# PCB_3U_SMA.net
KiCad netlist of a schematic drawn in Altium Designer
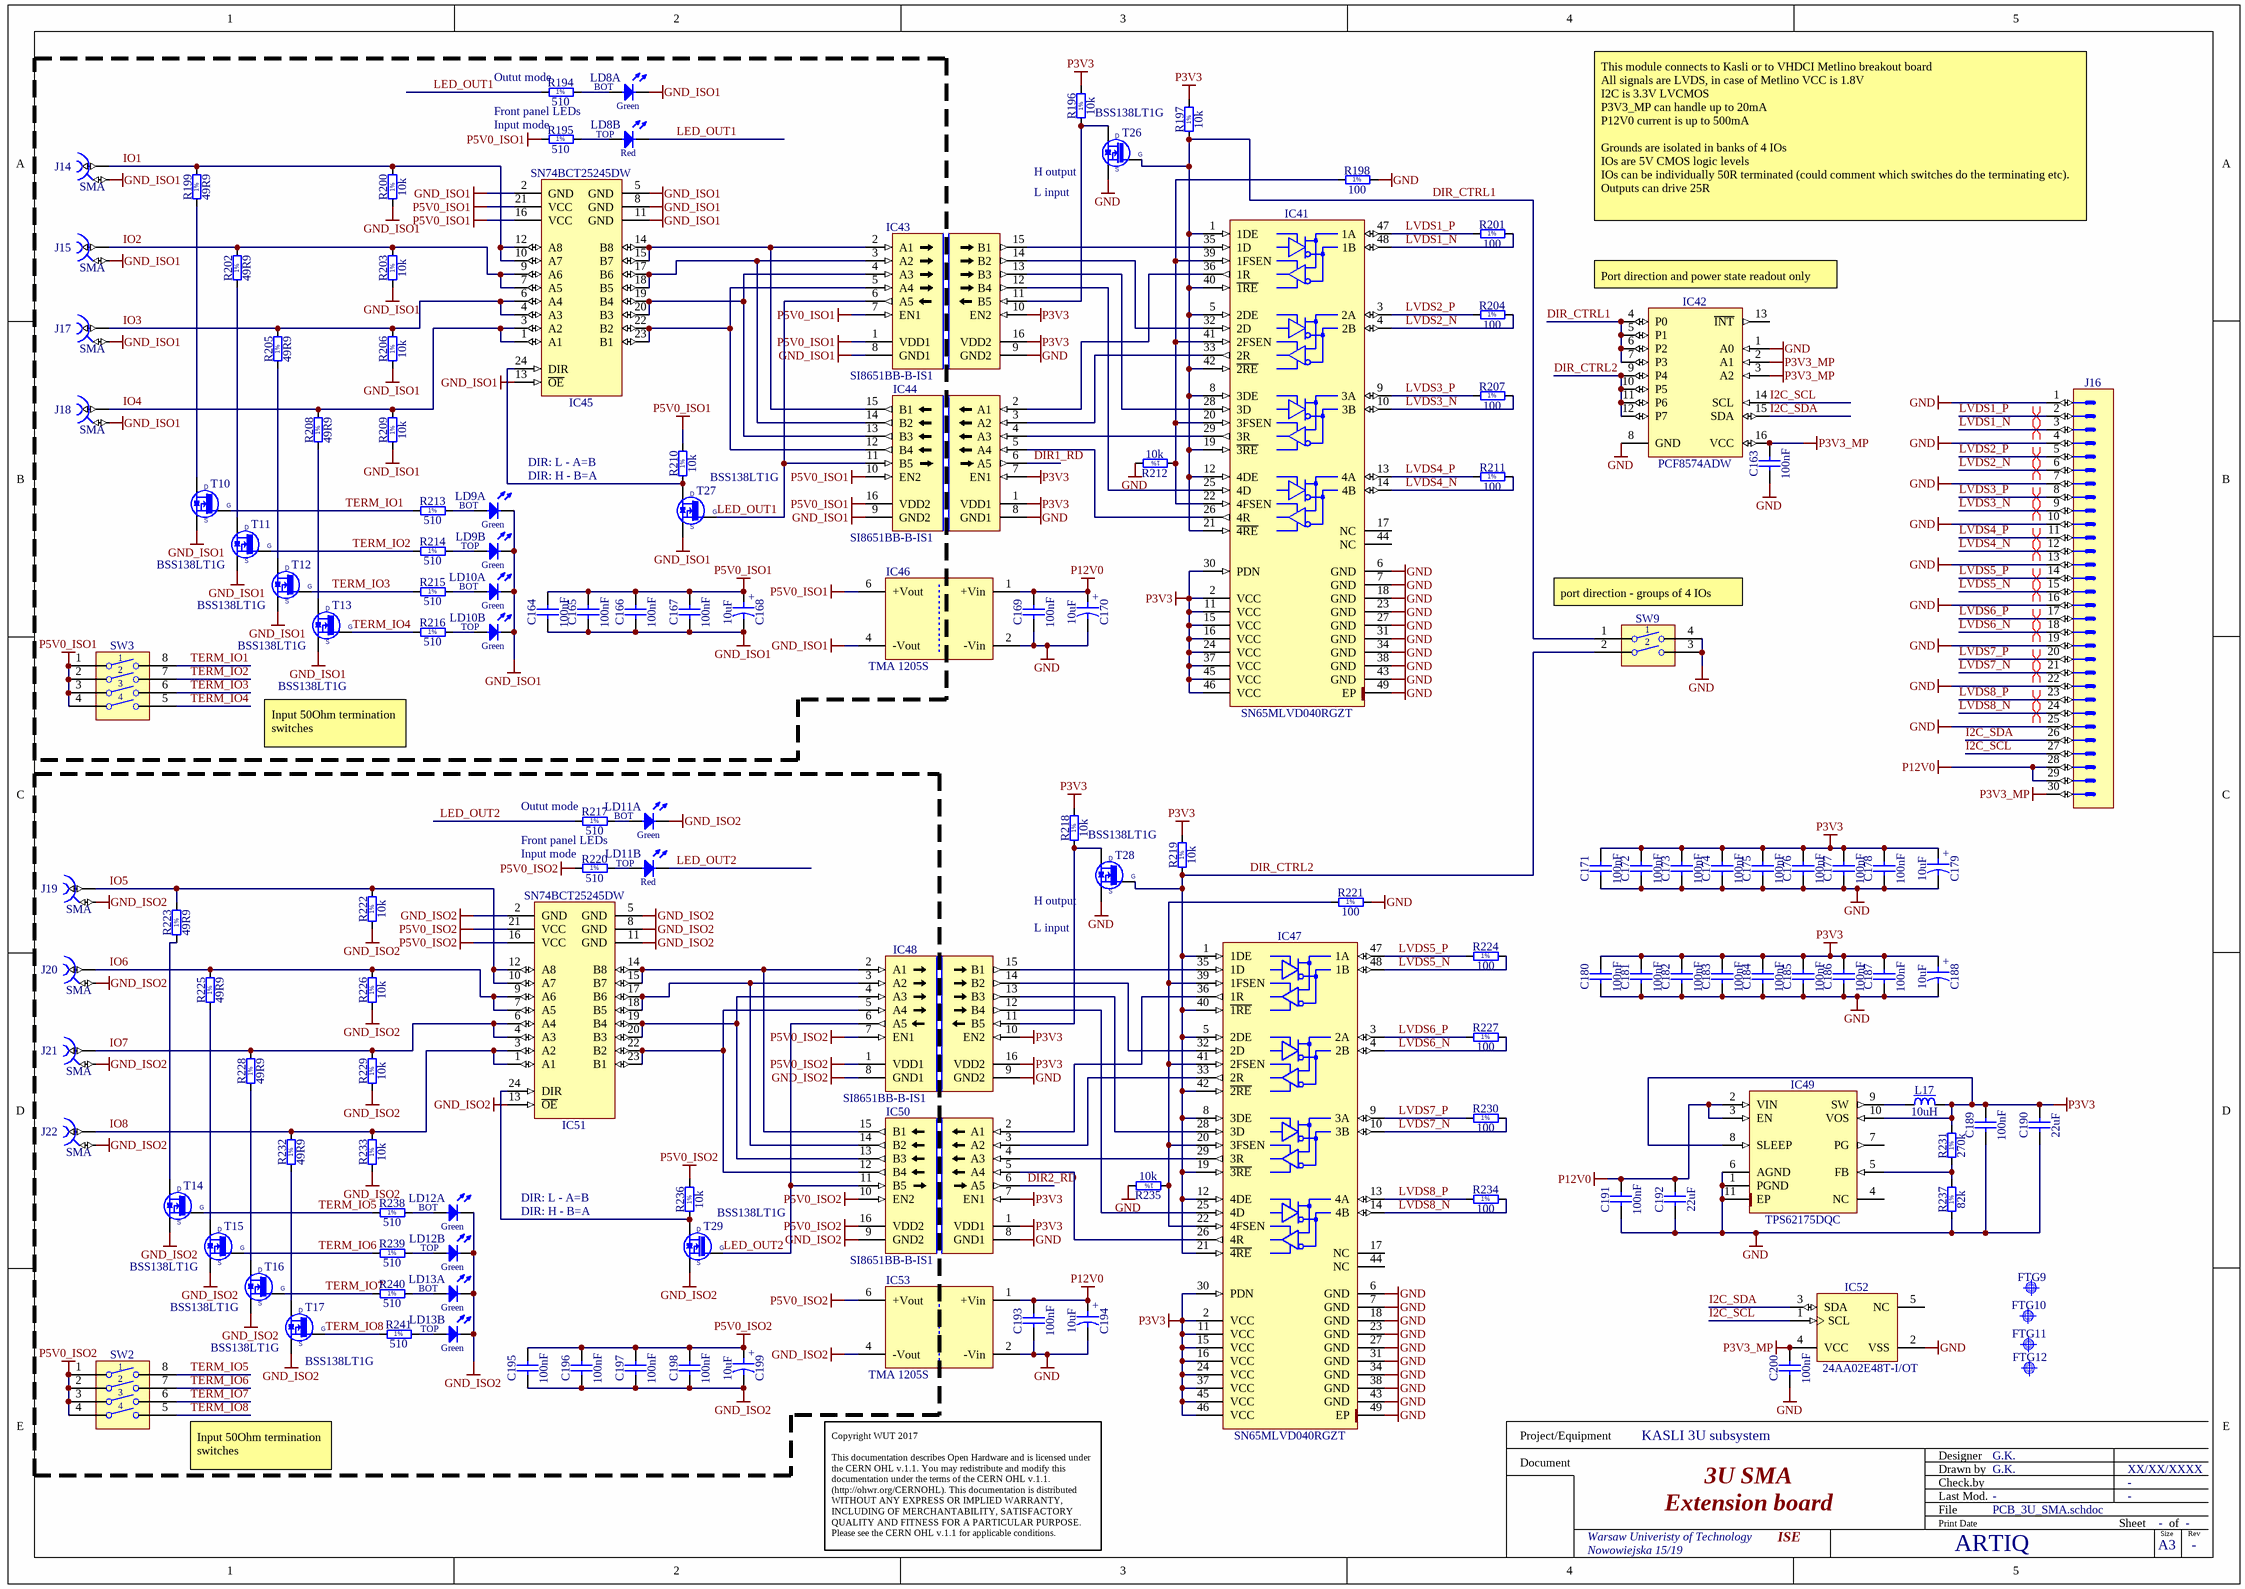
[diagram p0: PCB_3U_SMA.schdoc]

(export (version "E")
  (design (tool "Eeschema 10.0.6"))
  (components
    (comp (ref "C163")
      (value "100nF")
      (footprint "CAPC1005X55N")
      (description "Non-polarised capacitor")
      (fields
        (field (name "PART NUMBER") "CC0402_100NF_16V_10%_X5R")
        (field (name "VOLTAGE") "16V")
        (field (name "AUTHOR") "CERN DEM JLC")
      )
      (libsource (lib "Capacitors") (part "Capacitor - non polarized"))
    )
    (comp (ref "C164")
      (value "100nF")
      (footprint "CAPC1005X55N")
      (description "Non-polarised capacitor")
      (fields
        (field (name "PART NUMBER") "CC0402_100NF_16V_10%_X5R")
        (field (name "VOLTAGE") "16V")
        (field (name "AUTHOR") "CERN DEM JLC")
      )
      (libsource (lib "Capacitors") (part "Capacitor - non polarized"))
    )
    (comp (ref "C165")
      (value "100nF")
      (footprint "CAPC1005X55N")
      (description "Non-polarised capacitor")
      (fields
        (field (name "PART NUMBER") "CC0402_100NF_16V_10%_X5R")
        (field (name "VOLTAGE") "16V")
        (field (name "AUTHOR") "CERN DEM JLC")
      )
      (libsource (lib "Capacitors") (part "Capacitor - non polarized"))
    )
    (comp (ref "C166")
      (value "100nF")
      (footprint "CAPC1005X55N")
      (description "Non-polarised capacitor")
      (fields
        (field (name "PART NUMBER") "CC0402_100NF_16V_10%_X5R")
        (field (name "VOLTAGE") "16V")
        (field (name "AUTHOR") "CERN DEM JLC")
      )
      (libsource (lib "Capacitors") (part "Capacitor - non polarized"))
    )
    (comp (ref "C167")
      (value "100nF")
      (footprint "CAPC1005X55N")
      (description "Non-polarised capacitor")
      (fields
        (field (name "PART NUMBER") "CC0402_100NF_16V_10%_X5R")
        (field (name "VOLTAGE") "16V")
        (field (name "AUTHOR") "CERN DEM JLC")
      )
      (libsource (lib "Capacitors") (part "Capacitor - non polarized"))
    )
    (comp (ref "C168")
      (value "10uF")
      (footprint "CAPAE430X540N")
      (description "Polarised capacitor")
      (fields
        (field (name "PART NUMBER") "CAE430-540_10UF_16V_20%")
        (field (name "VOLTAGE") "16V")
        (field (name "AUTHOR") "CERN DEM JLC")
      )
      (libsource (lib "Capacitors") (part "Capacitor - polarized"))
    )
    (comp (ref "C169")
      (value "100nF")
      (footprint "CAPC1005X55N")
      (description "Non-polarised capacitor")
      (fields
        (field (name "PART NUMBER") "CC0402_100NF_16V_10%_X5R")
        (field (name "VOLTAGE") "16V")
        (field (name "AUTHOR") "CERN DEM JLC")
      )
      (libsource (lib "Capacitors") (part "Capacitor - non polarized"))
    )
    (comp (ref "C170")
      (value "10uF")
      (footprint "CAPAE430X540N")
      (description "Polarised capacitor")
      (fields
        (field (name "PART NUMBER") "CAE430-540_10UF_16V_20%")
        (field (name "VOLTAGE") "16V")
        (field (name "AUTHOR") "CERN DEM JLC")
      )
      (libsource (lib "Capacitors") (part "Capacitor - polarized"))
    )
    (comp (ref "C171")
      (value "100nF")
      (footprint "CAPC1005X55N")
      (description "Non-polarised capacitor")
      (fields
        (field (name "PART NUMBER") "CC0402_100NF_16V_10%_X5R")
        (field (name "VOLTAGE") "16V")
        (field (name "AUTHOR") "CERN DEM JLC")
      )
      (libsource (lib "Capacitors") (part "Capacitor - non polarized"))
    )
    (comp (ref "C172")
      (value "100nF")
      (footprint "CAPC1005X55N")
      (description "Non-polarised capacitor")
      (fields
        (field (name "PART NUMBER") "CC0402_100NF_16V_10%_X5R")
        (field (name "VOLTAGE") "16V")
        (field (name "AUTHOR") "CERN DEM JLC")
      )
      (libsource (lib "Capacitors") (part "Capacitor - non polarized"))
    )
    (comp (ref "C173")
      (value "100nF")
      (footprint "CAPC1005X55N")
      (description "Non-polarised capacitor")
      (fields
        (field (name "PART NUMBER") "CC0402_100NF_16V_10%_X5R")
        (field (name "VOLTAGE") "16V")
        (field (name "AUTHOR") "CERN DEM JLC")
      )
      (libsource (lib "Capacitors") (part "Capacitor - non polarized"))
    )
    (comp (ref "C174")
      (value "100nF")
      (footprint "CAPC1005X55N")
      (description "Non-polarised capacitor")
      (fields
        (field (name "PART NUMBER") "CC0402_100NF_16V_10%_X5R")
        (field (name "VOLTAGE") "16V")
        (field (name "AUTHOR") "CERN DEM JLC")
      )
      (libsource (lib "Capacitors") (part "Capacitor - non polarized"))
    )
    (comp (ref "C175")
      (value "100nF")
      (footprint "CAPC1005X55N")
      (description "Non-polarised capacitor")
      (fields
        (field (name "PART NUMBER") "CC0402_100NF_16V_10%_X5R")
        (field (name "VOLTAGE") "16V")
        (field (name "AUTHOR") "CERN DEM JLC")
      )
      (libsource (lib "Capacitors") (part "Capacitor - non polarized"))
    )
    (comp (ref "C176")
      (value "100nF")
      (footprint "CAPC1005X55N")
      (description "Non-polarised capacitor")
      (fields
        (field (name "PART NUMBER") "CC0402_100NF_16V_10%_X5R")
        (field (name "VOLTAGE") "16V")
        (field (name "AUTHOR") "CERN DEM JLC")
      )
      (libsource (lib "Capacitors") (part "Capacitor - non polarized"))
    )
    (comp (ref "C177")
      (value "100nF")
      (footprint "CAPC1005X55N")
      (description "Non-polarised capacitor")
      (fields
        (field (name "PART NUMBER") "CC0402_100NF_16V_10%_X5R")
        (field (name "VOLTAGE") "16V")
        (field (name "AUTHOR") "CERN DEM JLC")
      )
      (libsource (lib "Capacitors") (part "Capacitor - non polarized"))
    )
    (comp (ref "C178")
      (value "100nF")
      (footprint "CAPC1005X55N")
      (description "Non-polarised capacitor")
      (fields
        (field (name "PART NUMBER") "CC0402_100NF_16V_10%_X5R")
        (field (name "VOLTAGE") "16V")
        (field (name "AUTHOR") "CERN DEM JLC")
      )
      (libsource (lib "Capacitors") (part "Capacitor - non polarized"))
    )
    (comp (ref "C179")
      (value "10uF")
      (footprint "CAPAE430X540N")
      (description "Polarised capacitor")
      (fields
        (field (name "PART NUMBER") "CAE430-540_10UF_16V_20%")
        (field (name "VOLTAGE") "16V")
        (field (name "AUTHOR") "CERN DEM JLC")
      )
      (libsource (lib "Capacitors") (part "Capacitor - polarized"))
    )
    (comp (ref "C180")
      (value "100nF")
      (footprint "CAPC1005X55N")
      (description "Non-polarised capacitor")
      (fields
        (field (name "PART NUMBER") "CC0402_100NF_16V_10%_X5R")
        (field (name "VOLTAGE") "16V")
        (field (name "AUTHOR") "CERN DEM JLC")
      )
      (libsource (lib "Capacitors") (part "Capacitor - non polarized"))
    )
    (comp (ref "C181")
      (value "100nF")
      (footprint "CAPC1005X55N")
      (description "Non-polarised capacitor")
      (fields
        (field (name "PART NUMBER") "CC0402_100NF_16V_10%_X5R")
        (field (name "VOLTAGE") "16V")
        (field (name "AUTHOR") "CERN DEM JLC")
      )
      (libsource (lib "Capacitors") (part "Capacitor - non polarized"))
    )
    (comp (ref "C182")
      (value "100nF")
      (footprint "CAPC1005X55N")
      (description "Non-polarised capacitor")
      (fields
        (field (name "PART NUMBER") "CC0402_100NF_16V_10%_X5R")
        (field (name "VOLTAGE") "16V")
        (field (name "AUTHOR") "CERN DEM JLC")
      )
      (libsource (lib "Capacitors") (part "Capacitor - non polarized"))
    )
    (comp (ref "C183")
      (value "100nF")
      (footprint "CAPC1005X55N")
      (description "Non-polarised capacitor")
      (fields
        (field (name "PART NUMBER") "CC0402_100NF_16V_10%_X5R")
        (field (name "VOLTAGE") "16V")
        (field (name "AUTHOR") "CERN DEM JLC")
      )
      (libsource (lib "Capacitors") (part "Capacitor - non polarized"))
    )
    (comp (ref "C184")
      (value "100nF")
      (footprint "CAPC1005X55N")
      (description "Non-polarised capacitor")
      (fields
        (field (name "PART NUMBER") "CC0402_100NF_16V_10%_X5R")
        (field (name "VOLTAGE") "16V")
        (field (name "AUTHOR") "CERN DEM JLC")
      )
      (libsource (lib "Capacitors") (part "Capacitor - non polarized"))
    )
    (comp (ref "C185")
      (value "100nF")
      (footprint "CAPC1005X55N")
      (description "Non-polarised capacitor")
      (fields
        (field (name "PART NUMBER") "CC0402_100NF_16V_10%_X5R")
        (field (name "VOLTAGE") "16V")
        (field (name "AUTHOR") "CERN DEM JLC")
      )
      (libsource (lib "Capacitors") (part "Capacitor - non polarized"))
    )
    (comp (ref "C186")
      (value "100nF")
      (footprint "CAPC1005X55N")
      (description "Non-polarised capacitor")
      (fields
        (field (name "PART NUMBER") "CC0402_100NF_16V_10%_X5R")
        (field (name "VOLTAGE") "16V")
        (field (name "AUTHOR") "CERN DEM JLC")
      )
      (libsource (lib "Capacitors") (part "Capacitor - non polarized"))
    )
    (comp (ref "C187")
      (value "100nF")
      (footprint "CAPC1005X55N")
      (description "Non-polarised capacitor")
      (fields
        (field (name "PART NUMBER") "CC0402_100NF_16V_10%_X5R")
        (field (name "VOLTAGE") "16V")
        (field (name "AUTHOR") "CERN DEM JLC")
      )
      (libsource (lib "Capacitors") (part "Capacitor - non polarized"))
    )
    (comp (ref "C188")
      (value "10uF")
      (footprint "CAPAE430X540N")
      (description "Polarised capacitor")
      (fields
        (field (name "PART NUMBER") "CAE430-540_10UF_16V_20%")
        (field (name "VOLTAGE") "16V")
        (field (name "AUTHOR") "CERN DEM JLC")
      )
      (libsource (lib "Capacitors") (part "Capacitor - polarized"))
    )
    (comp (ref "C189")
      (value "100nF")
      (footprint "CAPC1005X55N")
      (description "Non-polarised capacitor")
      (fields
        (field (name "PART NUMBER") "CC0402_100NF_16V_10%_X5R")
        (field (name "VOLTAGE") "16V")
        (field (name "AUTHOR") "CERN DEM JLC")
      )
      (libsource (lib "Capacitors") (part "Capacitor - non polarized"))
    )
    (comp (ref "C190")
      (value "22uF")
      (footprint "CAPC2012X135N")
      (description "Non-polarised capacitor")
      (fields
        (field (name "PART NUMBER") "CC0805_22UF_16V_10%_X5R")
        (field (name "VOLTAGE") "16V")
        (field (name "AUTHOR") "CERN DEM JLC")
      )
      (libsource (lib "Capacitors") (part "Capacitor - non polarized"))
    )
    (comp (ref "C191")
      (value "100nF")
      (footprint "CAPC1005X55N")
      (description "Non-polarised capacitor")
      (fields
        (field (name "PART NUMBER") "CC0402_100NF_16V_10%_X5R")
        (field (name "VOLTAGE") "16V")
        (field (name "AUTHOR") "CERN DEM JLC")
      )
      (libsource (lib "Capacitors") (part "Capacitor - non polarized"))
    )
    (comp (ref "C192")
      (value "22uF")
      (footprint "CAPC2012X135N")
      (description "Non-polarised capacitor")
      (fields
        (field (name "PART NUMBER") "CC0805_22UF_16V_10%_X5R")
        (field (name "VOLTAGE") "16V")
        (field (name "AUTHOR") "CERN DEM JLC")
      )
      (libsource (lib "Capacitors") (part "Capacitor - non polarized"))
    )
    (comp (ref "C193")
      (value "100nF")
      (footprint "CAPC1005X55N")
      (description "Non-polarised capacitor")
      (fields
        (field (name "PART NUMBER") "CC0402_100NF_16V_10%_X5R")
        (field (name "VOLTAGE") "16V")
        (field (name "AUTHOR") "CERN DEM JLC")
      )
      (libsource (lib "Capacitors") (part "Capacitor - non polarized"))
    )
    (comp (ref "C194")
      (value "10uF")
      (footprint "CAPAE430X540N")
      (description "Polarised capacitor")
      (fields
        (field (name "PART NUMBER") "CAE430-540_10UF_16V_20%")
        (field (name "VOLTAGE") "16V")
        (field (name "AUTHOR") "CERN DEM JLC")
      )
      (libsource (lib "Capacitors") (part "Capacitor - polarized"))
    )
    (comp (ref "C195")
      (value "100nF")
      (footprint "CAPC1005X55N")
      (description "Non-polarised capacitor")
      (fields
        (field (name "PART NUMBER") "CC0402_100NF_16V_10%_X5R")
        (field (name "VOLTAGE") "16V")
        (field (name "AUTHOR") "CERN DEM JLC")
      )
      (libsource (lib "Capacitors") (part "Capacitor - non polarized"))
    )
    (comp (ref "C196")
      (value "100nF")
      (footprint "CAPC1005X55N")
      (description "Non-polarised capacitor")
      (fields
        (field (name "PART NUMBER") "CC0402_100NF_16V_10%_X5R")
        (field (name "VOLTAGE") "16V")
        (field (name "AUTHOR") "CERN DEM JLC")
      )
      (libsource (lib "Capacitors") (part "Capacitor - non polarized"))
    )
    (comp (ref "C197")
      (value "100nF")
      (footprint "CAPC1005X55N")
      (description "Non-polarised capacitor")
      (fields
        (field (name "PART NUMBER") "CC0402_100NF_16V_10%_X5R")
        (field (name "VOLTAGE") "16V")
        (field (name "AUTHOR") "CERN DEM JLC")
      )
      (libsource (lib "Capacitors") (part "Capacitor - non polarized"))
    )
    (comp (ref "C198")
      (value "100nF")
      (footprint "CAPC1005X55N")
      (description "Non-polarised capacitor")
      (fields
        (field (name "PART NUMBER") "CC0402_100NF_16V_10%_X5R")
        (field (name "VOLTAGE") "16V")
        (field (name "AUTHOR") "CERN DEM JLC")
      )
      (libsource (lib "Capacitors") (part "Capacitor - non polarized"))
    )
    (comp (ref "C199")
      (value "10uF")
      (footprint "CAPAE430X540N")
      (description "Polarised capacitor")
      (fields
        (field (name "PART NUMBER") "CAE430-540_10UF_16V_20%")
        (field (name "VOLTAGE") "16V")
        (field (name "AUTHOR") "CERN DEM JLC")
      )
      (libsource (lib "Capacitors") (part "Capacitor - polarized"))
    )
    (comp (ref "C200")
      (value "100nF")
      (footprint "CAPC1005X55N")
      (description "Non-polarised capacitor")
      (fields
        (field (name "PART NUMBER") "CC0402_100NF_16V_10%_X5R")
        (field (name "VOLTAGE") "16V")
        (field (name "AUTHOR") "CERN DEM JLC")
      )
      (libsource (lib "Capacitors") (part "Capacitor - non polarized"))
    )
    (comp (ref "FTG9")
      (value "Use only in PCB")
      (footprint "FIDUCIAL_TOP_C100-200")
      (description "Fiducial Target")
      (fields (field (name "PART NUMBER") "FIDUCIAL_TARGET_C100-200") (field (name "AUTHOR") "CERN DEM JLC"))
      (libsource (lib "Eletro-mechanical") (part "Fiducial Target"))
    )
    (comp (ref "FTG10")
      (value "Use only in PCB")
      (footprint "FIDUCIAL_TOP_S100-200")
      (description "Fiducial Target")
      (fields (field (name "PART NUMBER") "FIDUCIAL_TARGET_S100-200") (field (name "AUTHOR") "CERN DEM JLC"))
      (libsource (lib "Eletro-mechanical") (part "Fiducial Target"))
    )
    (comp (ref "FTG11")
      (value "Use only in PCB")
      (footprint "FIDUCIAL_TOP_S200-400")
      (description "Fiducial Target")
      (fields (field (name "PART NUMBER") "FIDUCIAL_TARGET_S200-400") (field (name "AUTHOR") "CERN DEM JLC"))
      (libsource (lib "Eletro-mechanical") (part "Fiducial Target"))
    )
    (comp (ref "FTG12")
      (value "Use only in PCB")
      (footprint "FIDUCIAL_TOP_S100-200")
      (description "Fiducial Target")
      (fields (field (name "PART NUMBER") "FIDUCIAL_TARGET_S100-200") (field (name "AUTHOR") "CERN DEM JLC"))
      (libsource (lib "Eletro-mechanical") (part "Fiducial Target"))
    )
    (comp (ref "IC41")
      (value "SN65MLVD040RGZT")
      (footprint "QFN50P700X700X100-49N-S420")
      (description "4-Channel Half-Duplex M-LVDS Line Transceiver")
      (fields (field (name "MANUFACTURER") "TEXAS INSTRUMENTS") (field (name "AUTHOR") "CERN DEM JLC"))
      (libsource (lib "ICs And Semiconductors") (part "SN65MLVD040"))
    )
    (comp (ref "IC42")
      (value "PCF8574ADW")
      (footprint "SOIC127P1030X265-16N")
      (description "Remote 8-bit I/O Expander For I2C Bus")
      (fields (field (name "MANUFACTURER") "TEXAS INSTRUMENTS") (field (name "AUTHOR") "CERN DEM JLC"))
      (libsource (lib "ICs And Semiconductors") (part "PCF8574ADW"))
    )
    (comp (ref "IC43")
      (value "SI8651BB-B-IS1")
      (footprint "SOIC127P600X175-16N")
      (description "Low Power Five-Channel Digital Isolator")
      (fields (field (name "MANUFACTURER") "SILICON LABS") (field (name "AUTHOR") "CERN DEM JLC"))
      (libsource (lib "") (part "Si8651_1"))
    )
    (comp (ref "IC44")
      (value "SI8651BB-B-IS1")
      (footprint "SOIC127P600X175-16N")
      (description "Low Power Five-Channel Digital Isolator")
      (fields (field (name "MANUFACTURER") "SILICON LABS") (field (name "AUTHOR") "CERN DEM JLC"))
      (libsource (lib "ICs And Semiconductors") (part "Si8651"))
    )
    (comp (ref "IC45")
      (value "SN74BCT25245DW")
      (footprint "SOIC127P1030X265-24N")
      (description "25 Ohms Octal Bus Transceiver With 3-State Outputs")
      (fields (field (name "MANUFACTURER") "TEXAS INSTRUMENTS") (field (name "AUTHOR") "CERN DEM JLC"))
      (libsource (lib "ICs And Semiconductors") (part "7425245"))
    )
    (comp (ref "IC46")
      (value "TMA 1205S")
      (footprint "DCDC_TRACO_TMA")
      (description "1 W Watt, 10.8-13.2VDCVin, 5 V@0.2 A")
      (fields (field (name "MANUFACTURER") "TRACO POWER") (field (name "AUTHOR") "GK"))
      (libsource (lib "LIBRARY_SCH") (part "DC/DC_TRACO_TMA1205S"))
    )
    (comp (ref "IC47")
      (value "SN65MLVD040RGZT")
      (footprint "QFN50P700X700X100-49N-S420")
      (description "4-Channel Half-Duplex M-LVDS Line Transceiver")
      (fields (field (name "MANUFACTURER") "TEXAS INSTRUMENTS") (field (name "AUTHOR") "CERN DEM JLC"))
      (libsource (lib "ICs And Semiconductors") (part "SN65MLVD040"))
    )
    (comp (ref "IC48")
      (value "SI8651BB-B-IS1")
      (footprint "SOIC127P600X175-16N")
      (description "Low Power Five-Channel Digital Isolator")
      (fields (field (name "MANUFACTURER") "SILICON LABS") (field (name "AUTHOR") "CERN DEM JLC"))
      (libsource (lib "") (part "Si8651_1"))
    )
    (comp (ref "IC49")
      (value "TPS62175DQC")
      (footprint "SON50P200X300X80-11N-R94X250")
      (description "4.75-28VDC to 1-6VDC, 500mA Step-Down Converter With Sleep Mode")
      (fields (field (name "MANUFACTURER") "TEXAS INSTRUMENTS") (field (name "AUTHOR") "CERN DEM JMW"))
      (libsource (lib "ICs And Semiconductors") (part "TPS62175"))
    )
    (comp (ref "IC50")
      (value "SI8651BB-B-IS1")
      (footprint "SOIC127P600X175-16N")
      (description "Low Power Five-Channel Digital Isolator")
      (fields (field (name "MANUFACTURER") "SILICON LABS") (field (name "AUTHOR") "CERN DEM JLC"))
      (libsource (lib "ICs And Semiconductors") (part "Si8651"))
    )
    (comp (ref "IC51")
      (value "SN74BCT25245DW")
      (footprint "SOIC127P1030X265-24N")
      (description "25 Ohms Octal Bus Transceiver With 3-State Outputs")
      (fields (field (name "MANUFACTURER") "TEXAS INSTRUMENTS") (field (name "AUTHOR") "CERN DEM JLC"))
      (libsource (lib "ICs And Semiconductors") (part "7425245"))
    )
    (comp (ref "IC52")
      (value "24AA02E48T-I/OT")
      (footprint "SOT95P280X145-5N")
      (description "1.7V-5.5V, 2K I2C Serial EEPROM With EUI-48 Node Identity")
      (fields (field (name "MANUFACTURER") "MICROCHIP TECHNOLOGY") (field (name "AUTHOR") "CERN DEM MR"))
      (libsource (lib "ICs And Semiconductors") (part "24AA02E48T-I/OT"))
    )
    (comp (ref "IC53")
      (value "TMA 1205S")
      (footprint "DCDC_TRACO_TMA")
      (description "1 W Watt, 10.8-13.2VDCVin, 5 V@0.2 A")
      (fields (field (name "MANUFACTURER") "TRACO POWER") (field (name "AUTHOR") "GK"))
      (libsource (lib "LIBRARY_SCH") (part "DC/DC_TRACO_TMA1205S"))
    )
    (comp (ref "J14")
      (value "SMA")
      (footprint "MOLEX_73251-2120")
      (description "50 Ohm, SMA Edge Mount PCB, With Jam Nut And Lock Washer")
      (fields
        (field (name "PART NUMBER") "MOLEX_73251-2120")
        (field (name "MANUFACTURER") "MOLEX")
        (field (name "AUTHOR") "CERN DEM JLC")
      )
      (libsource (lib "LIBRARY_SCH") (part "CON_SMA_RA_SMD_73251-2120"))
    )
    (comp (ref "J15")
      (value "SMA")
      (footprint "SMA209F")
      (description "50 Ohm Through Hole SMA Right Angle PCB Jack")
      (fields
        (field (name "PART NUMBER") "SMA209F")
        (field (name "MANUFACTURER") "S-Conn")
        (field (name "AUTHOR") "GK")
      )
      (libsource (lib "LIBRARY_SCH") (part "CON_SMA_SMA209F"))
    )
    (comp (ref "J16")
      (value "~")
      (footprint "3M_N2530-6002RB")
      (description "Connector 30 Male")
      (fields
        (field (name "PART NUMBER") "3M_N2530-6002RB")
        (field (name "MANUFACTURER") "3M")
        (field (name "AUTHOR") "CERN DEM JLC")
      )
      (libsource (lib "Connectors") (part "Connector 30 Male"))
    )
    (comp (ref "J17")
      (value "SMA")
      (footprint "MOLEX_73251-2120")
      (description "50 Ohm, SMA Edge Mount PCB, With Jam Nut And Lock Washer")
      (fields
        (field (name "PART NUMBER") "MOLEX_73251-2120")
        (field (name "MANUFACTURER") "MOLEX")
        (field (name "AUTHOR") "CERN DEM JLC")
      )
      (libsource (lib "LIBRARY_SCH") (part "CON_SMA_RA_SMD_73251-2120"))
    )
    (comp (ref "J18")
      (value "SMA")
      (footprint "SMA209F")
      (description "50 Ohm Through Hole SMA Right Angle PCB Jack")
      (fields
        (field (name "PART NUMBER") "SMA209F")
        (field (name "MANUFACTURER") "S-Conn")
        (field (name "AUTHOR") "GK")
      )
      (libsource (lib "LIBRARY_SCH") (part "CON_SMA_SMA209F"))
    )
    (comp (ref "J19")
      (value "SMA")
      (footprint "MOLEX_73251-2120")
      (description "50 Ohm, SMA Edge Mount PCB, With Jam Nut And Lock Washer")
      (fields
        (field (name "PART NUMBER") "MOLEX_73251-2120")
        (field (name "MANUFACTURER") "MOLEX")
        (field (name "AUTHOR") "CERN DEM JLC")
      )
      (libsource (lib "LIBRARY_SCH") (part "CON_SMA_RA_SMD_73251-2120"))
    )
    (comp (ref "J20")
      (value "SMA")
      (footprint "SMA209F")
      (description "50 Ohm Through Hole SMA Right Angle PCB Jack")
      (fields
        (field (name "PART NUMBER") "SMA209F")
        (field (name "MANUFACTURER") "S-Conn")
        (field (name "AUTHOR") "GK")
      )
      (libsource (lib "LIBRARY_SCH") (part "CON_SMA_SMA209F"))
    )
    (comp (ref "J21")
      (value "SMA")
      (footprint "MOLEX_73251-2120")
      (description "50 Ohm, SMA Edge Mount PCB, With Jam Nut And Lock Washer")
      (fields
        (field (name "PART NUMBER") "MOLEX_73251-2120")
        (field (name "MANUFACTURER") "MOLEX")
        (field (name "AUTHOR") "CERN DEM JLC")
      )
      (libsource (lib "LIBRARY_SCH") (part "CON_SMA_RA_SMD_73251-2120"))
    )
    (comp (ref "J22")
      (value "SMA")
      (footprint "SMA209F")
      (description "50 Ohm Through Hole SMA Right Angle PCB Jack")
      (fields
        (field (name "PART NUMBER") "SMA209F")
        (field (name "MANUFACTURER") "S-Conn")
        (field (name "AUTHOR") "GK")
      )
      (libsource (lib "LIBRARY_SCH") (part "CON_SMA_SMA209F"))
    )
    (comp (ref "L17")
      (value "10uH")
      (footprint "IND_MURATA-PS_8400")
      (description "Inductor With Core")
      (fields
        (field (name "PART NUMBER") "IND_10UH_10%_MURATA-PS_8400")
        (field (name "POWER") "950mA")
        (field (name "AUTHOR") "CERN DEM JLC")
      )
      (libsource (lib "Inductors & Transformers") (part "Inductor With Magnetic core"))
    )
    (comp (ref "LD8")
      (value "Red/Green")
      (footprint "LED_DIALIGHT_571-0112F")
      (description "2x LED  Botom Green, Top Red")
      (fields
        (field (name "PART NUMBER") "LED_DIALIGHT_571-0112F")
        (field (name "MANUFACTURER") "DIALIGHT")
        (field (name "AUTHOR") "CERN DEM JLC")
      )
      (libsource (lib "ICs And Semiconductors") (part "LED x2 G-1C2A-BOT_R-3C4A-TOP"))
    )
    (comp (ref "LD9")
      (value "Green/Green")
      (footprint "LED_DIALIGHT_571-0122F")
      (description "LED x2 Green 1C2A-BOT_3C4A-TOP")
      (fields
        (field (name "PART NUMBER") "LED_DIALIGHT_571-0122F")
        (field (name "MANUFACTURER") "DIALIGHT")
        (field (name "AUTHOR") "CERN DEM JLC")
      )
      (libsource (lib "ICs And Semiconductors") (part "LED x2 Green 1C2A-BOT_3C4A-TOP"))
    )
    (comp (ref "LD10")
      (value "Green/Green")
      (footprint "LED_DIALIGHT_571-0122F")
      (description "LED x2 Green 1C2A-BOT_3C4A-TOP")
      (fields
        (field (name "PART NUMBER") "LED_DIALIGHT_571-0122F")
        (field (name "MANUFACTURER") "DIALIGHT")
        (field (name "AUTHOR") "CERN DEM JLC")
      )
      (libsource (lib "ICs And Semiconductors") (part "LED x2 Green 1C2A-BOT_3C4A-TOP"))
    )
    (comp (ref "LD11")
      (value "Red/Green")
      (footprint "LED_DIALIGHT_571-0112F")
      (description "2x LED  Botom Green, Top Red")
      (fields
        (field (name "PART NUMBER") "LED_DIALIGHT_571-0112F")
        (field (name "MANUFACTURER") "DIALIGHT")
        (field (name "AUTHOR") "CERN DEM JLC")
      )
      (libsource (lib "ICs And Semiconductors") (part "LED x2 G-1C2A-BOT_R-3C4A-TOP"))
    )
    (comp (ref "LD12")
      (value "Green/Green")
      (footprint "LED_DIALIGHT_571-0122F")
      (description "LED x2 Green 1C2A-BOT_3C4A-TOP")
      (fields
        (field (name "PART NUMBER") "LED_DIALIGHT_571-0122F")
        (field (name "MANUFACTURER") "DIALIGHT")
        (field (name "AUTHOR") "CERN DEM JLC")
      )
      (libsource (lib "ICs And Semiconductors") (part "LED x2 Green 1C2A-BOT_3C4A-TOP"))
    )
    (comp (ref "LD13")
      (value "Green/Green")
      (footprint "LED_DIALIGHT_571-0122F")
      (description "LED x2 Green 1C2A-BOT_3C4A-TOP")
      (fields
        (field (name "PART NUMBER") "LED_DIALIGHT_571-0122F")
        (field (name "MANUFACTURER") "DIALIGHT")
        (field (name "AUTHOR") "CERN DEM JLC")
      )
      (libsource (lib "ICs And Semiconductors") (part "LED x2 Green 1C2A-BOT_3C4A-TOP"))
    )
    (comp (ref "R194")
      (value "510")
      (footprint "RESC1005X40N")
      (description "Resistor - 1%")
      (fields
        (field (name "PART NUMBER") "R0402_510R_1%_0.0625W_100PPM")
        (field (name "POWER") "0.0625W")
        (field (name "AUTHOR") "CERN DEM JLC")
      )
      (libsource (lib "Resistors") (part "Resistor - 1%"))
    )
    (comp (ref "R195")
      (value "510")
      (footprint "RESC1005X40N")
      (description "Resistor - 1%")
      (fields
        (field (name "PART NUMBER") "R0402_510R_1%_0.0625W_100PPM")
        (field (name "POWER") "0.0625W")
        (field (name "AUTHOR") "CERN DEM JLC")
      )
      (libsource (lib "Resistors") (part "Resistor - 1%"))
    )
    (comp (ref "R196")
      (value "10k")
      (footprint "RESC1005X40N")
      (description "Resistor - 1%")
      (fields
        (field (name "PART NUMBER") "R0402_10K_1%_0.0625W_100PPM")
        (field (name "POWER") "0.0625W")
        (field (name "AUTHOR") "CERN DEM JLC")
      )
      (libsource (lib "Resistors") (part "Resistor - 1%"))
    )
    (comp (ref "R197")
      (value "10k")
      (footprint "RESC1005X40N")
      (description "Resistor - 1%")
      (fields
        (field (name "PART NUMBER") "R0402_10K_1%_0.0625W_100PPM")
        (field (name "POWER") "0.0625W")
        (field (name "AUTHOR") "CERN DEM JLC")
      )
      (libsource (lib "Resistors") (part "Resistor - 1%"))
    )
    (comp (ref "R198")
      (value "100")
      (footprint "RESC1005X40N")
      (description "Resistor - 1%")
      (fields
        (field (name "PART NUMBER") "R0402_100R_1%_0.1W_100PPM")
        (field (name "POWER") "0.1W")
        (field (name "AUTHOR") "CERN DEM JLC")
      )
      (libsource (lib "Resistors") (part "Resistor - 1%"))
    )
    (comp (ref "R199")
      (value "49R9")
      (footprint "RESC3225X70N")
      (description "Resistor - 1%")
      (fields
        (field (name "PART NUMBER") "R1210_49R9_1%_0.5W_100PPM_VISHAY_CRCW")
        (field (name "POWER") "0.5W")
        (field (name "AUTHOR") "CERN DEM JMW")
      )
      (libsource (lib "Resistors") (part "Resistor - 1%"))
    )
    (comp (ref "R200")
      (value "10k")
      (footprint "RESC1005X40N")
      (description "Resistor - 1%")
      (fields
        (field (name "PART NUMBER") "R0402_10K_1%_0.0625W_100PPM")
        (field (name "POWER") "0.0625W")
        (field (name "AUTHOR") "CERN DEM JLC")
      )
      (libsource (lib "Resistors") (part "Resistor - 1%"))
    )
    (comp (ref "R201")
      (value "100")
      (footprint "RESC1005X40N")
      (description "Resistor - 1%")
      (fields
        (field (name "PART NUMBER") "R0402_100R_1%_0.1W_100PPM")
        (field (name "POWER") "0.1W")
        (field (name "AUTHOR") "CERN DEM JLC")
      )
      (libsource (lib "Resistors") (part "Resistor - 1%"))
    )
    (comp (ref "R202")
      (value "49R9")
      (footprint "RESC3225X70N")
      (description "Resistor - 1%")
      (fields
        (field (name "PART NUMBER") "R1210_49R9_1%_0.5W_100PPM_VISHAY_CRCW")
        (field (name "POWER") "0.5W")
        (field (name "AUTHOR") "CERN DEM JMW")
      )
      (libsource (lib "Resistors") (part "Resistor - 1%"))
    )
    (comp (ref "R203")
      (value "10k")
      (footprint "RESC1005X40N")
      (description "Resistor - 1%")
      (fields
        (field (name "PART NUMBER") "R0402_10K_1%_0.0625W_100PPM")
        (field (name "POWER") "0.0625W")
        (field (name "AUTHOR") "CERN DEM JLC")
      )
      (libsource (lib "Resistors") (part "Resistor - 1%"))
    )
    (comp (ref "R204")
      (value "100")
      (footprint "RESC1005X40N")
      (description "Resistor - 1%")
      (fields
        (field (name "PART NUMBER") "R0402_100R_1%_0.1W_100PPM")
        (field (name "POWER") "0.1W")
        (field (name "AUTHOR") "CERN DEM JLC")
      )
      (libsource (lib "Resistors") (part "Resistor - 1%"))
    )
    (comp (ref "R205")
      (value "49R9")
      (footprint "RESC3225X70N")
      (description "Resistor - 1%")
      (fields
        (field (name "PART NUMBER") "R1210_49R9_1%_0.5W_100PPM_VISHAY_CRCW")
        (field (name "POWER") "0.5W")
        (field (name "AUTHOR") "CERN DEM JMW")
      )
      (libsource (lib "Resistors") (part "Resistor - 1%"))
    )
    (comp (ref "R206")
      (value "10k")
      (footprint "RESC1005X40N")
      (description "Resistor - 1%")
      (fields
        (field (name "PART NUMBER") "R0402_10K_1%_0.0625W_100PPM")
        (field (name "POWER") "0.0625W")
        (field (name "AUTHOR") "CERN DEM JLC")
      )
      (libsource (lib "Resistors") (part "Resistor - 1%"))
    )
    (comp (ref "R207")
      (value "100")
      (footprint "RESC1005X40N")
      (description "Resistor - 1%")
      (fields
        (field (name "PART NUMBER") "R0402_100R_1%_0.1W_100PPM")
        (field (name "POWER") "0.1W")
        (field (name "AUTHOR") "CERN DEM JLC")
      )
      (libsource (lib "Resistors") (part "Resistor - 1%"))
    )
    (comp (ref "R208")
      (value "49R9")
      (footprint "RESC3225X70N")
      (description "Resistor - 1%")
      (fields
        (field (name "PART NUMBER") "R1210_49R9_1%_0.5W_100PPM_VISHAY_CRCW")
        (field (name "POWER") "0.5W")
        (field (name "AUTHOR") "CERN DEM JMW")
      )
      (libsource (lib "Resistors") (part "Resistor - 1%"))
    )
    (comp (ref "R209")
      (value "10k")
      (footprint "RESC1005X40N")
      (description "Resistor - 1%")
      (fields
        (field (name "PART NUMBER") "R0402_10K_1%_0.0625W_100PPM")
        (field (name "POWER") "0.0625W")
        (field (name "AUTHOR") "CERN DEM JLC")
      )
      (libsource (lib "Resistors") (part "Resistor - 1%"))
    )
    (comp (ref "R210")
      (value "10k")
      (footprint "RESC1005X40N")
      (description "Resistor - 1%")
      (fields
        (field (name "PART NUMBER") "R0402_10K_1%_0.0625W_100PPM")
        (field (name "POWER") "0.0625W")
        (field (name "AUTHOR") "CERN DEM JLC")
      )
      (libsource (lib "Resistors") (part "Resistor - 1%"))
    )
    (comp (ref "R211")
      (value "100")
      (footprint "RESC1005X40N")
      (description "Resistor - 1%")
      (fields
        (field (name "PART NUMBER") "R0402_100R_1%_0.1W_100PPM")
        (field (name "POWER") "0.1W")
        (field (name "AUTHOR") "CERN DEM JLC")
      )
      (libsource (lib "Resistors") (part "Resistor - 1%"))
    )
    (comp (ref "R212")
      (value "10k")
      (footprint "RESC1005X40N")
      (description "Resistor - 1%")
      (fields
        (field (name "PART NUMBER") "R0402_10K_1%_0.0625W_100PPM")
        (field (name "POWER") "0.0625W")
        (field (name "AUTHOR") "CERN DEM JLC")
      )
      (libsource (lib "Resistors") (part "Resistor - 1%"))
    )
    (comp (ref "R213")
      (value "510")
      (footprint "RESC1005X40N")
      (description "Resistor - 1%")
      (fields
        (field (name "PART NUMBER") "R0402_510R_1%_0.0625W_100PPM")
        (field (name "POWER") "0.0625W")
        (field (name "AUTHOR") "CERN DEM JLC")
      )
      (libsource (lib "Resistors") (part "Resistor - 1%"))
    )
    (comp (ref "R214")
      (value "510")
      (footprint "RESC1005X40N")
      (description "Resistor - 1%")
      (fields
        (field (name "PART NUMBER") "R0402_510R_1%_0.0625W_100PPM")
        (field (name "POWER") "0.0625W")
        (field (name "AUTHOR") "CERN DEM JLC")
      )
      (libsource (lib "Resistors") (part "Resistor - 1%"))
    )
    (comp (ref "R215")
      (value "510")
      (footprint "RESC1005X40N")
      (description "Resistor - 1%")
      (fields
        (field (name "PART NUMBER") "R0402_510R_1%_0.0625W_100PPM")
        (field (name "POWER") "0.0625W")
        (field (name "AUTHOR") "CERN DEM JLC")
      )
      (libsource (lib "Resistors") (part "Resistor - 1%"))
    )
    (comp (ref "R216")
      (value "510")
      (footprint "RESC1005X40N")
      (description "Resistor - 1%")
      (fields
        (field (name "PART NUMBER") "R0402_510R_1%_0.0625W_100PPM")
        (field (name "POWER") "0.0625W")
        (field (name "AUTHOR") "CERN DEM JLC")
      )
      (libsource (lib "Resistors") (part "Resistor - 1%"))
    )
    (comp (ref "R217")
      (value "510")
      (footprint "RESC1005X40N")
      (description "Resistor - 1%")
      (fields
        (field (name "PART NUMBER") "R0402_510R_1%_0.0625W_100PPM")
        (field (name "POWER") "0.0625W")
        (field (name "AUTHOR") "CERN DEM JLC")
      )
      (libsource (lib "Resistors") (part "Resistor - 1%"))
    )
    (comp (ref "R218")
      (value "10k")
      (footprint "RESC1005X40N")
      (description "Resistor - 1%")
      (fields
        (field (name "PART NUMBER") "R0402_10K_1%_0.0625W_100PPM")
        (field (name "POWER") "0.0625W")
        (field (name "AUTHOR") "CERN DEM JLC")
      )
      (libsource (lib "Resistors") (part "Resistor - 1%"))
    )
    (comp (ref "R219")
      (value "10k")
      (footprint "RESC1005X40N")
      (description "Resistor - 1%")
      (fields
        (field (name "PART NUMBER") "R0402_10K_1%_0.0625W_100PPM")
        (field (name "POWER") "0.0625W")
        (field (name "AUTHOR") "CERN DEM JLC")
      )
      (libsource (lib "Resistors") (part "Resistor - 1%"))
    )
    (comp (ref "R220")
      (value "510")
      (footprint "RESC1005X40N")
      (description "Resistor - 1%")
      (fields
        (field (name "PART NUMBER") "R0402_510R_1%_0.0625W_100PPM")
        (field (name "POWER") "0.0625W")
        (field (name "AUTHOR") "CERN DEM JLC")
      )
      (libsource (lib "Resistors") (part "Resistor - 1%"))
    )
    (comp (ref "R221")
      (value "100")
      (footprint "RESC1005X40N")
      (description "Resistor - 1%")
      (fields
        (field (name "PART NUMBER") "R0402_100R_1%_0.1W_100PPM")
        (field (name "POWER") "0.1W")
        (field (name "AUTHOR") "CERN DEM JLC")
      )
      (libsource (lib "Resistors") (part "Resistor - 1%"))
    )
    (comp (ref "R222")
      (value "10k")
      (footprint "RESC1005X40N")
      (description "Resistor - 1%")
      (fields
        (field (name "PART NUMBER") "R0402_10K_1%_0.0625W_100PPM")
        (field (name "POWER") "0.0625W")
        (field (name "AUTHOR") "CERN DEM JLC")
      )
      (libsource (lib "Resistors") (part "Resistor - 1%"))
    )
    (comp (ref "R223")
      (value "49R9")
      (footprint "RESC3225X70N")
      (description "Resistor - 1%")
      (fields
        (field (name "PART NUMBER") "R1210_49R9_1%_0.5W_100PPM_VISHAY_CRCW")
        (field (name "POWER") "0.5W")
        (field (name "AUTHOR") "CERN DEM JMW")
      )
      (libsource (lib "Resistors") (part "Resistor - 1%"))
    )
    (comp (ref "R224")
      (value "100")
      (footprint "RESC1005X40N")
      (description "Resistor - 1%")
      (fields
        (field (name "PART NUMBER") "R0402_100R_1%_0.1W_100PPM")
        (field (name "POWER") "0.1W")
        (field (name "AUTHOR") "CERN DEM JLC")
      )
      (libsource (lib "Resistors") (part "Resistor - 1%"))
    )
    (comp (ref "R225")
      (value "49R9")
      (footprint "RESC3225X70N")
      (description "Resistor - 1%")
      (fields
        (field (name "PART NUMBER") "R1210_49R9_1%_0.5W_100PPM_VISHAY_CRCW")
        (field (name "POWER") "0.5W")
        (field (name "AUTHOR") "CERN DEM JMW")
      )
      (libsource (lib "Resistors") (part "Resistor - 1%"))
    )
    (comp (ref "R226")
      (value "10k")
      (footprint "RESC1005X40N")
      (description "Resistor - 1%")
      (fields
        (field (name "PART NUMBER") "R0402_10K_1%_0.0625W_100PPM")
        (field (name "POWER") "0.0625W")
        (field (name "AUTHOR") "CERN DEM JLC")
      )
      (libsource (lib "Resistors") (part "Resistor - 1%"))
    )
    (comp (ref "R227")
      (value "100")
      (footprint "RESC1005X40N")
      (description "Resistor - 1%")
      (fields
        (field (name "PART NUMBER") "R0402_100R_1%_0.1W_100PPM")
        (field (name "POWER") "0.1W")
        (field (name "AUTHOR") "CERN DEM JLC")
      )
      (libsource (lib "Resistors") (part "Resistor - 1%"))
    )
    (comp (ref "R228")
      (value "49R9")
      (footprint "RESC3225X70N")
      (description "Resistor - 1%")
      (fields
        (field (name "PART NUMBER") "R1210_49R9_1%_0.5W_100PPM_VISHAY_CRCW")
        (field (name "POWER") "0.5W")
        (field (name "AUTHOR") "CERN DEM JMW")
      )
      (libsource (lib "Resistors") (part "Resistor - 1%"))
    )
    (comp (ref "R229")
      (value "10k")
      (footprint "RESC1005X40N")
      (description "Resistor - 1%")
      (fields
        (field (name "PART NUMBER") "R0402_10K_1%_0.0625W_100PPM")
        (field (name "POWER") "0.0625W")
        (field (name "AUTHOR") "CERN DEM JLC")
      )
      (libsource (lib "Resistors") (part "Resistor - 1%"))
    )
    (comp (ref "R230")
      (value "100")
      (footprint "RESC1005X40N")
      (description "Resistor - 1%")
      (fields
        (field (name "PART NUMBER") "R0402_100R_1%_0.1W_100PPM")
        (field (name "POWER") "0.1W")
        (field (name "AUTHOR") "CERN DEM JLC")
      )
      (libsource (lib "Resistors") (part "Resistor - 1%"))
    )
    (comp (ref "R231")
      (value "270k")
      (footprint "RESC1608X55N")
      (description "Resistor - 1%")
      (fields
        (field (name "PART NUMBER") "R0603_270K_1%_0.1W_100PPM")
        (field (name "POWER") "0.1W")
        (field (name "AUTHOR") "CERN DEM JLC")
      )
      (libsource (lib "Resistors") (part "Resistor - 1%"))
    )
    (comp (ref "R232")
      (value "49R9")
      (footprint "RESC3225X70N")
      (description "Resistor - 1%")
      (fields
        (field (name "PART NUMBER") "R1210_49R9_1%_0.5W_100PPM_VISHAY_CRCW")
        (field (name "POWER") "0.5W")
        (field (name "AUTHOR") "CERN DEM JMW")
      )
      (libsource (lib "Resistors") (part "Resistor - 1%"))
    )
    (comp (ref "R233")
      (value "10k")
      (footprint "RESC1005X40N")
      (description "Resistor - 1%")
      (fields
        (field (name "PART NUMBER") "R0402_10K_1%_0.0625W_100PPM")
        (field (name "POWER") "0.0625W")
        (field (name "AUTHOR") "CERN DEM JLC")
      )
      (libsource (lib "Resistors") (part "Resistor - 1%"))
    )
    (comp (ref "R234")
      (value "100")
      (footprint "RESC1005X40N")
      (description "Resistor - 1%")
      (fields
        (field (name "PART NUMBER") "R0402_100R_1%_0.1W_100PPM")
        (field (name "POWER") "0.1W")
        (field (name "AUTHOR") "CERN DEM JLC")
      )
      (libsource (lib "Resistors") (part "Resistor - 1%"))
    )
    (comp (ref "R235")
      (value "10k")
      (footprint "RESC1005X40N")
      (description "Resistor - 1%")
      (fields
        (field (name "PART NUMBER") "R0402_10K_1%_0.0625W_100PPM")
        (field (name "POWER") "0.0625W")
        (field (name "AUTHOR") "CERN DEM JLC")
      )
      (libsource (lib "Resistors") (part "Resistor - 1%"))
    )
    (comp (ref "R236")
      (value "10k")
      (footprint "RESC1005X40N")
      (description "Resistor - 1%")
      (fields
        (field (name "PART NUMBER") "R0402_10K_1%_0.0625W_100PPM")
        (field (name "POWER") "0.0625W")
        (field (name "AUTHOR") "CERN DEM JLC")
      )
      (libsource (lib "Resistors") (part "Resistor - 1%"))
    )
    (comp (ref "R237")
      (value "82k")
      (footprint "RESC1608X55N")
      (description "Resistor - 1%")
      (fields
        (field (name "PART NUMBER") "R0603_82K_1%_0.1W_100PPM")
        (field (name "POWER") "0.1W")
        (field (name "AUTHOR") "CERN DEM JLC")
      )
      (libsource (lib "Resistors") (part "Resistor - 1%"))
    )
    (comp (ref "R238")
      (value "510")
      (footprint "RESC1005X40N")
      (description "Resistor - 1%")
      (fields
        (field (name "PART NUMBER") "R0402_510R_1%_0.0625W_100PPM")
        (field (name "POWER") "0.0625W")
        (field (name "AUTHOR") "CERN DEM JLC")
      )
      (libsource (lib "Resistors") (part "Resistor - 1%"))
    )
    (comp (ref "R239")
      (value "510")
      (footprint "RESC1005X40N")
      (description "Resistor - 1%")
      (fields
        (field (name "PART NUMBER") "R0402_510R_1%_0.0625W_100PPM")
        (field (name "POWER") "0.0625W")
        (field (name "AUTHOR") "CERN DEM JLC")
      )
      (libsource (lib "Resistors") (part "Resistor - 1%"))
    )
    (comp (ref "R240")
      (value "510")
      (footprint "RESC1005X40N")
      (description "Resistor - 1%")
      (fields
        (field (name "PART NUMBER") "R0402_510R_1%_0.0625W_100PPM")
        (field (name "POWER") "0.0625W")
        (field (name "AUTHOR") "CERN DEM JLC")
      )
      (libsource (lib "Resistors") (part "Resistor - 1%"))
    )
    (comp (ref "R241")
      (value "510")
      (footprint "RESC1005X40N")
      (description "Resistor - 1%")
      (fields
        (field (name "PART NUMBER") "R0402_510R_1%_0.0625W_100PPM")
        (field (name "POWER") "0.0625W")
        (field (name "AUTHOR") "CERN DEM JLC")
      )
      (libsource (lib "Resistors") (part "Resistor - 1%"))
    )
    (comp (ref "SW2")
      (value "Switch")
      (footprint "SW_OMRON_A6S-4102-H")
      (description "4 Ways SPST DIP Switch")
      (fields
        (field (name "PART NUMBER") "SW_OMRON_A6S-4102-H")
        (field (name "MANUFACTURER") "OMRON")
        (field (name "AUTHOR") "CERN DEM JMW")
      )
      (libsource (lib "Eletro-mechanical") (part "SW 4x SPST DIP Switch"))
    )
    (comp (ref "SW3")
      (value "Switch")
      (footprint "SW_OMRON_A6S-4102-H")
      (description "4 Ways SPST DIP Switch")
      (fields
        (field (name "PART NUMBER") "SW_OMRON_A6S-4102-H")
        (field (name "MANUFACTURER") "OMRON")
        (field (name "AUTHOR") "CERN DEM JMW")
      )
      (libsource (lib "Eletro-mechanical") (part "SW 4x SPST DIP Switch"))
    )
    (comp (ref "SW9")
      (value "Switch")
      (footprint "SW_OMRON_A6S-2102-H")
      (description "2 Ways SPST DIP Switch")
      (fields
        (field (name "PART NUMBER") "SW_OMRON_A6S-2102-H")
        (field (name "MANUFACTURER") "OMRON")
        (field (name "AUTHOR") "CERN DEM JMW")
      )
      (libsource (lib "Eletro-mechanical") (part "SW 2x SPST DIP Switch"))
    )
    (comp (ref "T10")
      (value "BSS138LT1G")
      (footprint "SOT95P240X110-3N")
      (description "N-CHANNEL MOSFET WITH DIODE")
      (fields (field (name "MANUFACTURER") "ON SEMICONDUCTOR") (field (name "AUTHOR") "CERN DEM JLC"))
      (libsource (lib "ICs And Semiconductors") (part "N-MOSFET-D 1G 2S 3D"))
    )
    (comp (ref "T11")
      (value "BSS138LT1G")
      (footprint "SOT95P240X110-3N")
      (description "N-CHANNEL MOSFET WITH DIODE")
      (fields (field (name "MANUFACTURER") "ON SEMICONDUCTOR") (field (name "AUTHOR") "CERN DEM JLC"))
      (libsource (lib "ICs And Semiconductors") (part "N-MOSFET-D 1G 2S 3D"))
    )
    (comp (ref "T12")
      (value "BSS138LT1G")
      (footprint "SOT95P240X110-3N")
      (description "N-CHANNEL MOSFET WITH DIODE")
      (fields (field (name "MANUFACTURER") "ON SEMICONDUCTOR") (field (name "AUTHOR") "CERN DEM JLC"))
      (libsource (lib "ICs And Semiconductors") (part "N-MOSFET-D 1G 2S 3D"))
    )
    (comp (ref "T13")
      (value "BSS138LT1G")
      (footprint "SOT95P240X110-3N")
      (description "N-CHANNEL MOSFET WITH DIODE")
      (fields (field (name "MANUFACTURER") "ON SEMICONDUCTOR") (field (name "AUTHOR") "CERN DEM JLC"))
      (libsource (lib "ICs And Semiconductors") (part "N-MOSFET-D 1G 2S 3D"))
    )
    (comp (ref "T14")
      (value "BSS138LT1G")
      (footprint "SOT95P240X110-3N")
      (description "N-CHANNEL MOSFET WITH DIODE")
      (fields (field (name "MANUFACTURER") "ON SEMICONDUCTOR") (field (name "AUTHOR") "CERN DEM JLC"))
      (libsource (lib "ICs And Semiconductors") (part "N-MOSFET-D 1G 2S 3D"))
    )
    (comp (ref "T15")
      (value "BSS138LT1G")
      (footprint "SOT95P240X110-3N")
      (description "N-CHANNEL MOSFET WITH DIODE")
      (fields (field (name "MANUFACTURER") "ON SEMICONDUCTOR") (field (name "AUTHOR") "CERN DEM JLC"))
      (libsource (lib "ICs And Semiconductors") (part "N-MOSFET-D 1G 2S 3D"))
    )
    (comp (ref "T16")
      (value "BSS138LT1G")
      (footprint "SOT95P240X110-3N")
      (description "N-CHANNEL MOSFET WITH DIODE")
      (fields (field (name "MANUFACTURER") "ON SEMICONDUCTOR") (field (name "AUTHOR") "CERN DEM JLC"))
      (libsource (lib "ICs And Semiconductors") (part "N-MOSFET-D 1G 2S 3D"))
    )
    (comp (ref "T17")
      (value "BSS138LT1G")
      (footprint "SOT95P240X110-3N")
      (description "N-CHANNEL MOSFET WITH DIODE")
      (fields (field (name "MANUFACTURER") "ON SEMICONDUCTOR") (field (name "AUTHOR") "CERN DEM JLC"))
      (libsource (lib "ICs And Semiconductors") (part "N-MOSFET-D 1G 2S 3D"))
    )
    (comp (ref "T26")
      (value "BSS138LT1G")
      (footprint "SOT95P240X110-3N")
      (description "N-CHANNEL MOSFET WITH DIODE")
      (fields (field (name "MANUFACTURER") "ON SEMICONDUCTOR") (field (name "AUTHOR") "CERN DEM JLC"))
      (libsource (lib "ICs And Semiconductors") (part "N-MOSFET-D 1G 2S 3D"))
    )
    (comp (ref "T27")
      (value "BSS138LT1G")
      (footprint "SOT95P240X110-3N")
      (description "N-CHANNEL MOSFET WITH DIODE")
      (fields (field (name "MANUFACTURER") "ON SEMICONDUCTOR") (field (name "AUTHOR") "CERN DEM JLC"))
      (libsource (lib "ICs And Semiconductors") (part "N-MOSFET-D 1G 2S 3D"))
    )
    (comp (ref "T28")
      (value "BSS138LT1G")
      (footprint "SOT95P240X110-3N")
      (description "N-CHANNEL MOSFET WITH DIODE")
      (fields (field (name "MANUFACTURER") "ON SEMICONDUCTOR") (field (name "AUTHOR") "CERN DEM JLC"))
      (libsource (lib "ICs And Semiconductors") (part "N-MOSFET-D 1G 2S 3D"))
    )
    (comp (ref "T29")
      (value "BSS138LT1G")
      (footprint "SOT95P240X110-3N")
      (description "N-CHANNEL MOSFET WITH DIODE")
      (fields (field (name "MANUFACTURER") "ON SEMICONDUCTOR") (field (name "AUTHOR") "CERN DEM JLC"))
      (libsource (lib "ICs And Semiconductors") (part "N-MOSFET-D 1G 2S 3D"))
    )
  )
  (nets
    (net (code "1") (name "/DIR1_RD") (class "Default")
      (node (ref "IC44") (pin "6") (pinfunction "A5_6") (pintype "output"))
    )
    (net (code "2") (name "/DIR2_RD") (class "Default")
      (node (ref "IC50") (pin "6") (pinfunction "A5_6") (pintype "output"))
    )
    (net (code "3") (name "/DIR_CTRL1") (class "Default")
      (node (ref "IC41") (pin "1") (pinfunction "1DE_1") (pintype "input"))
      (node (ref "IC41") (pin "12") (pinfunction "4DE_12") (pintype "input"))
      (node (ref "IC41") (pin "19") (pinfunction "~{3RE}_19") (pintype "input"))
      (node (ref "IC41") (pin "21") (pinfunction "~{4RE}_21") (pintype "input"))
      (node (ref "IC41") (pin "40") (pinfunction "~{1RE}_40") (pintype "input"))
      (node (ref "IC41") (pin "42") (pinfunction "~{2RE}_42") (pintype "input"))
      (node (ref "IC41") (pin "5") (pinfunction "2DE_5") (pintype "input"))
      (node (ref "IC41") (pin "8") (pinfunction "3DE_8") (pintype "input"))
      (node (ref "IC42") (pin "4") (pinfunction "P0_4") (pintype "bidirectional"))
      (node (ref "IC42") (pin "5") (pinfunction "P1_5") (pintype "bidirectional"))
      (node (ref "IC42") (pin "6") (pinfunction "P2_6") (pintype "bidirectional"))
      (node (ref "IC42") (pin "7") (pinfunction "P3_7") (pintype "bidirectional"))
      (node (ref "R197") (pin "1") (pinfunction "1_1") (pintype "passive"))
      (node (ref "SW9") (pin "1") (pinfunction "1_1") (pintype "passive"))
      (node (ref "T26") (pin "1") (pinfunction "G_1") (pintype "passive"))
    )
    (net (code "4") (name "/DIR_CTRL2") (class "Default")
      (node (ref "IC42") (pin "10") (pinfunction "P5_10") (pintype "bidirectional"))
      (node (ref "IC42") (pin "11") (pinfunction "P6_11") (pintype "bidirectional"))
      (node (ref "IC42") (pin "12") (pinfunction "P7_12") (pintype "bidirectional"))
      (node (ref "IC42") (pin "9") (pinfunction "P4_9") (pintype "bidirectional"))
      (node (ref "IC47") (pin "1") (pinfunction "1DE_1") (pintype "input"))
      (node (ref "IC47") (pin "12") (pinfunction "4DE_12") (pintype "input"))
      (node (ref "IC47") (pin "19") (pinfunction "~{3RE}_19") (pintype "input"))
      (node (ref "IC47") (pin "21") (pinfunction "~{4RE}_21") (pintype "input"))
      (node (ref "IC47") (pin "40") (pinfunction "~{1RE}_40") (pintype "input"))
      (node (ref "IC47") (pin "42") (pinfunction "~{2RE}_42") (pintype "input"))
      (node (ref "IC47") (pin "5") (pinfunction "2DE_5") (pintype "input"))
      (node (ref "IC47") (pin "8") (pinfunction "3DE_8") (pintype "input"))
      (node (ref "R219") (pin "1") (pinfunction "1_1") (pintype "passive"))
      (node (ref "SW9") (pin "2") (pinfunction "2_2") (pintype "passive"))
      (node (ref "T28") (pin "1") (pinfunction "G_1") (pintype "passive"))
    )
    (net (code "5") (name "/I2C_SCL") (class "Default")
      (node (ref "IC42") (pin "14") (pinfunction "SCL_14") (pintype "input"))
      (node (ref "IC52") (pin "1") (pinfunction "SCL_1") (pintype "input"))
      (node (ref "J16") (pin "27") (pinfunction "27_27") (pintype "bidirectional"))
    )
    (net (code "6") (name "/I2C_SDA") (class "Default")
      (node (ref "IC42") (pin "15") (pinfunction "SDA_15") (pintype "bidirectional"))
      (node (ref "IC52") (pin "3") (pinfunction "SDA_3") (pintype "bidirectional"))
      (node (ref "J16") (pin "26") (pinfunction "26_26") (pintype "bidirectional"))
    )
    (net (code "7") (name "/IO1") (class "Default")
      (node (ref "IC45") (pin "10") (pinfunction "A7_10") (pintype "bidirectional"))
      (node (ref "IC45") (pin "12") (pinfunction "A8_12") (pintype "bidirectional"))
      (node (ref "J14") (pin "1") (pinfunction "1_1") (pintype "bidirectional"))
      (node (ref "R199") (pin "2") (pinfunction "2_2") (pintype "passive"))
      (node (ref "R200") (pin "2") (pinfunction "2_2") (pintype "passive"))
    )
    (net (code "8") (name "/IO2") (class "Default")
      (node (ref "IC45") (pin "7") (pinfunction "A5_7") (pintype "bidirectional"))
      (node (ref "IC45") (pin "9") (pinfunction "A6_9") (pintype "bidirectional"))
      (node (ref "J15") (pin "1") (pinfunction "1_1") (pintype "bidirectional"))
      (node (ref "R202") (pin "2") (pinfunction "2_2") (pintype "passive"))
      (node (ref "R203") (pin "2") (pinfunction "2_2") (pintype "passive"))
    )
    (net (code "9") (name "/IO3") (class "Default")
      (node (ref "IC45") (pin "4") (pinfunction "A3_4") (pintype "bidirectional"))
      (node (ref "IC45") (pin "6") (pinfunction "A4_6") (pintype "bidirectional"))
      (node (ref "J17") (pin "1") (pinfunction "1_1") (pintype "bidirectional"))
      (node (ref "R205") (pin "2") (pinfunction "2_2") (pintype "passive"))
      (node (ref "R206") (pin "2") (pinfunction "2_2") (pintype "passive"))
    )
    (net (code "10") (name "/IO4") (class "Default")
      (node (ref "IC45") (pin "1") (pinfunction "A1_1") (pintype "bidirectional"))
      (node (ref "IC45") (pin "3") (pinfunction "A2_3") (pintype "bidirectional"))
      (node (ref "J18") (pin "1") (pinfunction "1_1") (pintype "bidirectional"))
      (node (ref "R208") (pin "2") (pinfunction "2_2") (pintype "passive"))
      (node (ref "R209") (pin "2") (pinfunction "2_2") (pintype "passive"))
    )
    (net (code "11") (name "/IO5") (class "Default")
      (node (ref "IC51") (pin "10") (pinfunction "A7_10") (pintype "bidirectional"))
      (node (ref "IC51") (pin "12") (pinfunction "A8_12") (pintype "bidirectional"))
      (node (ref "J19") (pin "1") (pinfunction "1_1") (pintype "bidirectional"))
      (node (ref "R222") (pin "2") (pinfunction "2_2") (pintype "passive"))
      (node (ref "R223") (pin "2") (pinfunction "2_2") (pintype "passive"))
    )
    (net (code "12") (name "/IO6") (class "Default")
      (node (ref "IC51") (pin "7") (pinfunction "A5_7") (pintype "bidirectional"))
      (node (ref "IC51") (pin "9") (pinfunction "A6_9") (pintype "bidirectional"))
      (node (ref "J20") (pin "1") (pinfunction "1_1") (pintype "bidirectional"))
      (node (ref "R225") (pin "2") (pinfunction "2_2") (pintype "passive"))
      (node (ref "R226") (pin "2") (pinfunction "2_2") (pintype "passive"))
    )
    (net (code "13") (name "/IO7") (class "Default")
      (node (ref "IC51") (pin "4") (pinfunction "A3_4") (pintype "bidirectional"))
      (node (ref "IC51") (pin "6") (pinfunction "A4_6") (pintype "bidirectional"))
      (node (ref "J21") (pin "1") (pinfunction "1_1") (pintype "bidirectional"))
      (node (ref "R228") (pin "2") (pinfunction "2_2") (pintype "passive"))
      (node (ref "R229") (pin "2") (pinfunction "2_2") (pintype "passive"))
    )
    (net (code "14") (name "/IO8") (class "Default")
      (node (ref "IC51") (pin "1") (pinfunction "A1_1") (pintype "bidirectional"))
      (node (ref "IC51") (pin "3") (pinfunction "A2_3") (pintype "bidirectional"))
      (node (ref "J22") (pin "1") (pinfunction "1_1") (pintype "bidirectional"))
      (node (ref "R232") (pin "2") (pinfunction "2_2") (pintype "passive"))
      (node (ref "R233") (pin "2") (pinfunction "2_2") (pintype "passive"))
    )
    (net (code "15") (name "/LED_OUT1") (class "Default")
      (node (ref "IC43") (pin "6") (pinfunction "A5_6") (pintype "output"))
      (node (ref "IC44") (pin "11") (pinfunction "B5_11") (pintype "input"))
      (node (ref "LD8") (pin "3") (pinfunction "C_3") (pintype "passive"))
      (node (ref "R194") (pin "1") (pinfunction "1_1") (pintype "passive"))
      (node (ref "T27") (pin "1") (pinfunction "G_1") (pintype "passive"))
    )
    (net (code "16") (name "/LED_OUT2") (class "Default")
      (node (ref "IC48") (pin "6") (pinfunction "A5_6") (pintype "output"))
      (node (ref "IC50") (pin "11") (pinfunction "B5_11") (pintype "input"))
      (node (ref "LD11") (pin "3") (pinfunction "C_3") (pintype "passive"))
      (node (ref "R217") (pin "1") (pinfunction "1_1") (pintype "passive"))
      (node (ref "T29") (pin "1") (pinfunction "G_1") (pintype "passive"))
    )
    (net (code "17") (name "/LVDS1_N") (class "Default")
      (node (ref "IC41") (pin "48") (pinfunction "1B_48") (pintype "bidirectional"))
      (node (ref "J16") (pin "3") (pinfunction "3_3") (pintype "bidirectional"))
      (node (ref "R201") (pin "2") (pinfunction "2_2") (pintype "passive"))
    )
    (net (code "18") (name "/LVDS1_P") (class "Default")
      (node (ref "IC41") (pin "47") (pinfunction "1A_47") (pintype "bidirectional"))
      (node (ref "J16") (pin "2") (pinfunction "2_2") (pintype "bidirectional"))
      (node (ref "R201") (pin "1") (pinfunction "1_1") (pintype "passive"))
    )
    (net (code "19") (name "/LVDS2_N") (class "Default")
      (node (ref "IC41") (pin "4") (pinfunction "2B_4") (pintype "bidirectional"))
      (node (ref "J16") (pin "6") (pinfunction "6_6") (pintype "bidirectional"))
      (node (ref "R204") (pin "2") (pinfunction "2_2") (pintype "passive"))
    )
    (net (code "20") (name "/LVDS2_P") (class "Default")
      (node (ref "IC41") (pin "3") (pinfunction "2A_3") (pintype "bidirectional"))
      (node (ref "J16") (pin "5") (pinfunction "5_5") (pintype "bidirectional"))
      (node (ref "R204") (pin "1") (pinfunction "1_1") (pintype "passive"))
    )
    (net (code "21") (name "/LVDS3_N") (class "Default")
      (node (ref "IC41") (pin "10") (pinfunction "3B_10") (pintype "bidirectional"))
      (node (ref "J16") (pin "9") (pinfunction "9_9") (pintype "bidirectional"))
      (node (ref "R207") (pin "2") (pinfunction "2_2") (pintype "passive"))
    )
    (net (code "22") (name "/LVDS3_P") (class "Default")
      (node (ref "IC41") (pin "9") (pinfunction "3A_9") (pintype "bidirectional"))
      (node (ref "J16") (pin "8") (pinfunction "8_8") (pintype "bidirectional"))
      (node (ref "R207") (pin "1") (pinfunction "1_1") (pintype "passive"))
    )
    (net (code "23") (name "/LVDS4_N") (class "Default")
      (node (ref "IC41") (pin "14") (pinfunction "4B_14") (pintype "bidirectional"))
      (node (ref "J16") (pin "12") (pinfunction "12_12") (pintype "bidirectional"))
      (node (ref "R211") (pin "2") (pinfunction "2_2") (pintype "passive"))
    )
    (net (code "24") (name "/LVDS4_P") (class "Default")
      (node (ref "IC41") (pin "13") (pinfunction "4A_13") (pintype "bidirectional"))
      (node (ref "J16") (pin "11") (pinfunction "11_11") (pintype "bidirectional"))
      (node (ref "R211") (pin "1") (pinfunction "1_1") (pintype "passive"))
    )
    (net (code "25") (name "/LVDS5_N") (class "Default")
      (node (ref "IC47") (pin "48") (pinfunction "1B_48") (pintype "bidirectional"))
      (node (ref "J16") (pin "15") (pinfunction "15_15") (pintype "bidirectional"))
      (node (ref "R224") (pin "2") (pinfunction "2_2") (pintype "passive"))
    )
    (net (code "26") (name "/LVDS5_P") (class "Default")
      (node (ref "IC47") (pin "47") (pinfunction "1A_47") (pintype "bidirectional"))
      (node (ref "J16") (pin "14") (pinfunction "14_14") (pintype "bidirectional"))
      (node (ref "R224") (pin "1") (pinfunction "1_1") (pintype "passive"))
    )
    (net (code "27") (name "/LVDS6_N") (class "Default")
      (node (ref "IC47") (pin "4") (pinfunction "2B_4") (pintype "bidirectional"))
      (node (ref "J16") (pin "18") (pinfunction "18_18") (pintype "bidirectional"))
      (node (ref "R227") (pin "2") (pinfunction "2_2") (pintype "passive"))
    )
    (net (code "28") (name "/LVDS6_P") (class "Default")
      (node (ref "IC47") (pin "3") (pinfunction "2A_3") (pintype "bidirectional"))
      (node (ref "J16") (pin "17") (pinfunction "17_17") (pintype "bidirectional"))
      (node (ref "R227") (pin "1") (pinfunction "1_1") (pintype "passive"))
    )
    (net (code "29") (name "/LVDS7_N") (class "Default")
      (node (ref "IC47") (pin "10") (pinfunction "3B_10") (pintype "bidirectional"))
      (node (ref "J16") (pin "21") (pinfunction "21_21") (pintype "bidirectional"))
      (node (ref "R230") (pin "2") (pinfunction "2_2") (pintype "passive"))
    )
    (net (code "30") (name "/LVDS7_P") (class "Default")
      (node (ref "IC47") (pin "9") (pinfunction "3A_9") (pintype "bidirectional"))
      (node (ref "J16") (pin "20") (pinfunction "20_20") (pintype "bidirectional"))
      (node (ref "R230") (pin "1") (pinfunction "1_1") (pintype "passive"))
    )
    (net (code "31") (name "/LVDS8_N") (class "Default")
      (node (ref "IC47") (pin "14") (pinfunction "4B_14") (pintype "bidirectional"))
      (node (ref "J16") (pin "24") (pinfunction "24_24") (pintype "bidirectional"))
      (node (ref "R234") (pin "2") (pinfunction "2_2") (pintype "passive"))
    )
    (net (code "32") (name "/LVDS8_P") (class "Default")
      (node (ref "IC47") (pin "13") (pinfunction "4A_13") (pintype "bidirectional"))
      (node (ref "J16") (pin "23") (pinfunction "23_23") (pintype "bidirectional"))
      (node (ref "R234") (pin "1") (pinfunction "1_1") (pintype "passive"))
    )
    (net (code "33") (name "/TERM_IO1") (class "Default")
      (node (ref "R213") (pin "1") (pinfunction "1_1") (pintype "passive"))
      (node (ref "SW3") (pin "8") (pinfunction "8_8") (pintype "passive"))
      (node (ref "T10") (pin "1") (pinfunction "G_1") (pintype "passive"))
    )
    (net (code "34") (name "/TERM_IO2") (class "Default")
      (node (ref "R214") (pin "1") (pinfunction "1_1") (pintype "passive"))
      (node (ref "SW3") (pin "7") (pinfunction "7_7") (pintype "passive"))
      (node (ref "T11") (pin "1") (pinfunction "G_1") (pintype "passive"))
    )
    (net (code "35") (name "/TERM_IO3") (class "Default")
      (node (ref "R215") (pin "1") (pinfunction "1_1") (pintype "passive"))
      (node (ref "SW3") (pin "6") (pinfunction "6_6") (pintype "passive"))
      (node (ref "T12") (pin "1") (pinfunction "G_1") (pintype "passive"))
    )
    (net (code "36") (name "/TERM_IO4") (class "Default")
      (node (ref "R216") (pin "1") (pinfunction "1_1") (pintype "passive"))
      (node (ref "SW3") (pin "5") (pinfunction "5_5") (pintype "passive"))
      (node (ref "T13") (pin "1") (pinfunction "G_1") (pintype "passive"))
    )
    (net (code "37") (name "/TERM_IO5") (class "Default")
      (node (ref "R238") (pin "1") (pinfunction "1_1") (pintype "passive"))
      (node (ref "SW2") (pin "8") (pinfunction "8_8") (pintype "passive"))
      (node (ref "T14") (pin "1") (pinfunction "G_1") (pintype "passive"))
    )
    (net (code "38") (name "/TERM_IO6") (class "Default")
      (node (ref "R239") (pin "1") (pinfunction "1_1") (pintype "passive"))
      (node (ref "SW2") (pin "7") (pinfunction "7_7") (pintype "passive"))
      (node (ref "T15") (pin "1") (pinfunction "G_1") (pintype "passive"))
    )
    (net (code "39") (name "/TERM_IO7") (class "Default")
      (node (ref "R240") (pin "1") (pinfunction "1_1") (pintype "passive"))
      (node (ref "SW2") (pin "6") (pinfunction "6_6") (pintype "passive"))
      (node (ref "T16") (pin "1") (pinfunction "G_1") (pintype "passive"))
    )
    (net (code "40") (name "/TERM_IO8") (class "Default")
      (node (ref "R241") (pin "1") (pinfunction "1_1") (pintype "passive"))
      (node (ref "SW2") (pin "5") (pinfunction "5_5") (pintype "passive"))
      (node (ref "T17") (pin "1") (pinfunction "G_1") (pintype "passive"))
    )
    (net (code "41") (name "GND") (class "Default")
      (node (ref "C163") (pin "1") (pinfunction "1_1") (pintype "passive"))
      (node (ref "C169") (pin "1") (pinfunction "1_1") (pintype "passive"))
      (node (ref "C170") (pin "2") (pinfunction "2_2") (pintype "passive"))
      (node (ref "C171") (pin "1") (pinfunction "1_1") (pintype "passive"))
      (node (ref "C172") (pin "1") (pinfunction "1_1") (pintype "passive"))
      (node (ref "C173") (pin "1") (pinfunction "1_1") (pintype "passive"))
      (node (ref "C174") (pin "1") (pinfunction "1_1") (pintype "passive"))
      (node (ref "C175") (pin "1") (pinfunction "1_1") (pintype "passive"))
      (node (ref "C176") (pin "1") (pinfunction "1_1") (pintype "passive"))
      (node (ref "C177") (pin "1") (pinfunction "1_1") (pintype "passive"))
      (node (ref "C178") (pin "1") (pinfunction "1_1") (pintype "passive"))
      (node (ref "C179") (pin "2") (pinfunction "2_2") (pintype "passive"))
      (node (ref "C180") (pin "1") (pinfunction "1_1") (pintype "passive"))
      (node (ref "C181") (pin "1") (pinfunction "1_1") (pintype "passive"))
      (node (ref "C182") (pin "1") (pinfunction "1_1") (pintype "passive"))
      (node (ref "C183") (pin "1") (pinfunction "1_1") (pintype "passive"))
      (node (ref "C184") (pin "1") (pinfunction "1_1") (pintype "passive"))
      (node (ref "C185") (pin "1") (pinfunction "1_1") (pintype "passive"))
      (node (ref "C186") (pin "1") (pinfunction "1_1") (pintype "passive"))
      (node (ref "C187") (pin "1") (pinfunction "1_1") (pintype "passive"))
      (node (ref "C188") (pin "2") (pinfunction "2_2") (pintype "passive"))
      (node (ref "C189") (pin "1") (pinfunction "1_1") (pintype "passive"))
      (node (ref "C190") (pin "1") (pinfunction "1_1") (pintype "passive"))
      (node (ref "C191") (pin "1") (pinfunction "1_1") (pintype "passive"))
      (node (ref "C192") (pin "1") (pinfunction "1_1") (pintype "passive"))
      (node (ref "C193") (pin "1") (pinfunction "1_1") (pintype "passive"))
      (node (ref "C194") (pin "2") (pinfunction "2_2") (pintype "passive"))
      (node (ref "C200") (pin "1") (pinfunction "1_1") (pintype "passive"))
      (node (ref "IC41") (pin "18") (pinfunction "GND_18") (pintype "power_in"))
      (node (ref "IC41") (pin "23") (pinfunction "GND_23") (pintype "power_in"))
      (node (ref "IC41") (pin "27") (pinfunction "GND_27") (pintype "power_in"))
      (node (ref "IC41") (pin "31") (pinfunction "GND_31") (pintype "power_in"))
      (node (ref "IC41") (pin "34") (pinfunction "GND_34") (pintype "power_in"))
      (node (ref "IC41") (pin "38") (pinfunction "GND_38") (pintype "power_in"))
      (node (ref "IC41") (pin "43") (pinfunction "GND_43") (pintype "power_in"))
      (node (ref "IC41") (pin "49") (pinfunction "EP_49") (pintype "power_in"))
      (node (ref "IC41") (pin "6") (pinfunction "GND_6") (pintype "power_in"))
      (node (ref "IC41") (pin "7") (pinfunction "GND_7") (pintype "power_in"))
      (node (ref "IC42") (pin "1") (pinfunction "A0_1") (pintype "input"))
      (node (ref "IC42") (pin "8") (pinfunction "GND_8") (pintype "power_in"))
      (node (ref "IC43") (pin "9") (pinfunction "GND2_9") (pintype "power_in"))
      (node (ref "IC44") (pin "8") (pinfunction "GND1_8") (pintype "power_in"))
      (node (ref "IC46") (pin "2") (pinfunction "-Vin_2") (pintype "power_in"))
      (node (ref "IC47") (pin "18") (pinfunction "GND_18") (pintype "power_in"))
      (node (ref "IC47") (pin "23") (pinfunction "GND_23") (pintype "power_in"))
      (node (ref "IC47") (pin "27") (pinfunction "GND_27") (pintype "power_in"))
      (node (ref "IC47") (pin "31") (pinfunction "GND_31") (pintype "power_in"))
      (node (ref "IC47") (pin "34") (pinfunction "GND_34") (pintype "power_in"))
      (node (ref "IC47") (pin "38") (pinfunction "GND_38") (pintype "power_in"))
      (node (ref "IC47") (pin "43") (pinfunction "GND_43") (pintype "power_in"))
      (node (ref "IC47") (pin "49") (pinfunction "EP_49") (pintype "power_in"))
      (node (ref "IC47") (pin "6") (pinfunction "GND_6") (pintype "power_in"))
      (node (ref "IC47") (pin "7") (pinfunction "GND_7") (pintype "power_in"))
      (node (ref "IC48") (pin "9") (pinfunction "GND2_9") (pintype "power_in"))
      (node (ref "IC49") (pin "1") (pinfunction "PGND_1") (pintype "power_in"))
      (node (ref "IC49") (pin "11") (pinfunction "EP_11") (pintype "power_in"))
      (node (ref "IC49") (pin "6") (pinfunction "AGND_6") (pintype "power_in"))
      (node (ref "IC50") (pin "8") (pinfunction "GND1_8") (pintype "power_in"))
      (node (ref "IC52") (pin "2") (pinfunction "VSS_2") (pintype "power_in"))
      (node (ref "IC53") (pin "2") (pinfunction "-Vin_2") (pintype "power_in"))
      (node (ref "J16") (pin "1") (pinfunction "1_1") (pintype "bidirectional"))
      (node (ref "J16") (pin "10") (pinfunction "10_10") (pintype "bidirectional"))
      (node (ref "J16") (pin "13") (pinfunction "13_13") (pintype "bidirectional"))
      (node (ref "J16") (pin "16") (pinfunction "16_16") (pintype "bidirectional"))
      (node (ref "J16") (pin "19") (pinfunction "19_19") (pintype "bidirectional"))
      (node (ref "J16") (pin "22") (pinfunction "22_22") (pintype "bidirectional"))
      (node (ref "J16") (pin "25") (pinfunction "25_25") (pintype "bidirectional"))
      (node (ref "J16") (pin "4") (pinfunction "4_4") (pintype "bidirectional"))
      (node (ref "J16") (pin "7") (pinfunction "7_7") (pintype "bidirectional"))
      (node (ref "R198") (pin "2") (pinfunction "2_2") (pintype "passive"))
      (node (ref "R212") (pin "2") (pinfunction "2_2") (pintype "passive"))
      (node (ref "R221") (pin "2") (pinfunction "2_2") (pintype "passive"))
      (node (ref "R235") (pin "2") (pinfunction "2_2") (pintype "passive"))
      (node (ref "R237") (pin "1") (pinfunction "1_1") (pintype "passive"))
      (node (ref "SW9") (pin "3") (pinfunction "3_3") (pintype "passive"))
      (node (ref "SW9") (pin "4") (pinfunction "4_4") (pintype "passive"))
      (node (ref "T26") (pin "2") (pinfunction "S_2") (pintype "passive"))
      (node (ref "T28") (pin "2") (pinfunction "S_2") (pintype "passive"))
    )
    (net (code "42") (name "GND_ISO1") (class "Default")
      (node (ref "C164") (pin "1") (pinfunction "1_1") (pintype "passive"))
      (node (ref "C165") (pin "1") (pinfunction "1_1") (pintype "passive"))
      (node (ref "C166") (pin "1") (pinfunction "1_1") (pintype "passive"))
      (node (ref "C167") (pin "1") (pinfunction "1_1") (pintype "passive"))
      (node (ref "C168") (pin "2") (pinfunction "2_2") (pintype "passive"))
      (node (ref "IC43") (pin "8") (pinfunction "GND1_8") (pintype "power_in"))
      (node (ref "IC44") (pin "9") (pinfunction "GND2_9") (pintype "power_in"))
      (node (ref "IC45") (pin "11") (pinfunction "GND_11") (pintype "power_in"))
      (node (ref "IC45") (pin "13") (pinfunction "OE_13") (pintype "input"))
      (node (ref "IC45") (pin "2") (pinfunction "GND_2") (pintype "power_in"))
      (node (ref "IC45") (pin "5") (pinfunction "GND_5") (pintype "power_in"))
      (node (ref "IC45") (pin "8") (pinfunction "GND_8") (pintype "power_in"))
      (node (ref "IC46") (pin "4") (pinfunction "-Vout_4") (pintype "power_in"))
      (node (ref "J14") (pin "2") (pinfunction "2_2") (pintype "bidirectional"))
      (node (ref "J15") (pin "2") (pinfunction "2_2") (pintype "bidirectional"))
      (node (ref "J17") (pin "2") (pinfunction "2_2") (pintype "bidirectional"))
      (node (ref "J18") (pin "2") (pinfunction "2_2") (pintype "bidirectional"))
      (node (ref "LD10") (pin "1") (pinfunction "C_1") (pintype "passive"))
      (node (ref "LD10") (pin "3") (pinfunction "C_3") (pintype "passive"))
      (node (ref "LD8") (pin "1") (pinfunction "C_1") (pintype "passive"))
      (node (ref "LD9") (pin "1") (pinfunction "C_1") (pintype "passive"))
      (node (ref "LD9") (pin "3") (pinfunction "C_3") (pintype "passive"))
      (node (ref "R200") (pin "1") (pinfunction "1_1") (pintype "passive"))
      (node (ref "R203") (pin "1") (pinfunction "1_1") (pintype "passive"))
      (node (ref "R206") (pin "1") (pinfunction "1_1") (pintype "passive"))
      (node (ref "R209") (pin "1") (pinfunction "1_1") (pintype "passive"))
      (node (ref "T10") (pin "2") (pinfunction "S_2") (pintype "passive"))
      (node (ref "T11") (pin "2") (pinfunction "S_2") (pintype "passive"))
      (node (ref "T12") (pin "2") (pinfunction "S_2") (pintype "passive"))
      (node (ref "T13") (pin "2") (pinfunction "S_2") (pintype "passive"))
      (node (ref "T27") (pin "2") (pinfunction "S_2") (pintype "passive"))
    )
    (net (code "43") (name "GND_ISO2") (class "Default")
      (node (ref "C195") (pin "1") (pinfunction "1_1") (pintype "passive"))
      (node (ref "C196") (pin "1") (pinfunction "1_1") (pintype "passive"))
      (node (ref "C197") (pin "1") (pinfunction "1_1") (pintype "passive"))
      (node (ref "C198") (pin "1") (pinfunction "1_1") (pintype "passive"))
      (node (ref "C199") (pin "2") (pinfunction "2_2") (pintype "passive"))
      (node (ref "IC48") (pin "8") (pinfunction "GND1_8") (pintype "power_in"))
      (node (ref "IC50") (pin "9") (pinfunction "GND2_9") (pintype "power_in"))
      (node (ref "IC51") (pin "11") (pinfunction "GND_11") (pintype "power_in"))
      (node (ref "IC51") (pin "13") (pinfunction "OE_13") (pintype "input"))
      (node (ref "IC51") (pin "2") (pinfunction "GND_2") (pintype "power_in"))
      (node (ref "IC51") (pin "5") (pinfunction "GND_5") (pintype "power_in"))
      (node (ref "IC51") (pin "8") (pinfunction "GND_8") (pintype "power_in"))
      (node (ref "IC53") (pin "4") (pinfunction "-Vout_4") (pintype "power_in"))
      (node (ref "J19") (pin "2") (pinfunction "2_2") (pintype "bidirectional"))
      (node (ref "J20") (pin "2") (pinfunction "2_2") (pintype "bidirectional"))
      (node (ref "J21") (pin "2") (pinfunction "2_2") (pintype "bidirectional"))
      (node (ref "J22") (pin "2") (pinfunction "2_2") (pintype "bidirectional"))
      (node (ref "LD11") (pin "1") (pinfunction "C_1") (pintype "passive"))
      (node (ref "LD12") (pin "1") (pinfunction "C_1") (pintype "passive"))
      (node (ref "LD12") (pin "3") (pinfunction "C_3") (pintype "passive"))
      (node (ref "LD13") (pin "1") (pinfunction "C_1") (pintype "passive"))
      (node (ref "LD13") (pin "3") (pinfunction "C_3") (pintype "passive"))
      (node (ref "R222") (pin "1") (pinfunction "1_1") (pintype "passive"))
      (node (ref "R226") (pin "1") (pinfunction "1_1") (pintype "passive"))
      (node (ref "R229") (pin "1") (pinfunction "1_1") (pintype "passive"))
      (node (ref "R233") (pin "1") (pinfunction "1_1") (pintype "passive"))
      (node (ref "T14") (pin "2") (pinfunction "S_2") (pintype "passive"))
      (node (ref "T15") (pin "2") (pinfunction "S_2") (pintype "passive"))
      (node (ref "T16") (pin "2") (pinfunction "S_2") (pintype "passive"))
      (node (ref "T17") (pin "2") (pinfunction "S_2") (pintype "passive"))
      (node (ref "T29") (pin "2") (pinfunction "S_2") (pintype "passive"))
    )
    (net (code "44") (name "Net-(IC41-1D)") (class "Default")
      (node (ref "IC41") (pin "35") (pinfunction "1D_35") (pintype "input"))
      (node (ref "IC43") (pin "15") (pinfunction "B1_15") (pintype "output"))
    )
    (net (code "45") (name "Net-(IC41-1FSEN)") (class "Default")
      (node (ref "IC41") (pin "20") (pinfunction "3FSEN_20") (pintype "input"))
      (node (ref "IC41") (pin "22") (pinfunction "4FSEN_22") (pintype "input"))
      (node (ref "IC41") (pin "39") (pinfunction "1FSEN_39") (pintype "input"))
      (node (ref "IC41") (pin "41") (pinfunction "2FSEN_41") (pintype "input"))
      (node (ref "R198") (pin "1") (pinfunction "1_1") (pintype "passive"))
      (node (ref "R212") (pin "1") (pinfunction "1_1") (pintype "passive"))
    )
    (net (code "46") (name "Net-(IC41-1R)") (class "Default")
      (node (ref "IC41") (pin "36") (pinfunction "1R_36") (pintype "output"))
      (node (ref "IC44") (pin "2") (pinfunction "A1_2") (pintype "input"))
    )
    (net (code "47") (name "Net-(IC41-2D)") (class "Default")
      (node (ref "IC41") (pin "32") (pinfunction "2D_32") (pintype "input"))
      (node (ref "IC43") (pin "14") (pinfunction "B2_14") (pintype "output"))
    )
    (net (code "48") (name "Net-(IC41-2R)") (class "Default")
      (node (ref "IC41") (pin "33") (pinfunction "2R_33") (pintype "output"))
      (node (ref "IC44") (pin "3") (pinfunction "A2_3") (pintype "input"))
    )
    (net (code "49") (name "Net-(IC41-3D)") (class "Default")
      (node (ref "IC41") (pin "28") (pinfunction "3D_28") (pintype "input"))
      (node (ref "IC43") (pin "13") (pinfunction "B3_13") (pintype "output"))
    )
    (net (code "50") (name "Net-(IC41-3R)") (class "Default")
      (node (ref "IC41") (pin "29") (pinfunction "3R_29") (pintype "output"))
      (node (ref "IC44") (pin "4") (pinfunction "A3_4") (pintype "input"))
    )
    (net (code "51") (name "Net-(IC41-4D)") (class "Default")
      (node (ref "IC41") (pin "25") (pinfunction "4D_25") (pintype "input"))
      (node (ref "IC43") (pin "12") (pinfunction "B4_12") (pintype "output"))
    )
    (net (code "52") (name "Net-(IC41-4R)") (class "Default")
      (node (ref "IC41") (pin "26") (pinfunction "4R_26") (pintype "output"))
      (node (ref "IC44") (pin "5") (pinfunction "A4_5") (pintype "input"))
    )
    (net (code "53") (name "Net-(IC43-A1)") (class "Default")
      (node (ref "IC43") (pin "2") (pinfunction "A1_2") (pintype "input"))
      (node (ref "IC44") (pin "15") (pinfunction "B1_15") (pintype "output"))
      (node (ref "IC45") (pin "14") (pinfunction "B8_14") (pintype "bidirectional"))
      (node (ref "IC45") (pin "15") (pinfunction "B7_15") (pintype "bidirectional"))
    )
    (net (code "54") (name "Net-(IC43-A2)") (class "Default")
      (node (ref "IC43") (pin "3") (pinfunction "A2_3") (pintype "input"))
      (node (ref "IC44") (pin "14") (pinfunction "B2_14") (pintype "output"))
      (node (ref "IC45") (pin "17") (pinfunction "B6_17") (pintype "bidirectional"))
      (node (ref "IC45") (pin "18") (pinfunction "B5_18") (pintype "bidirectional"))
    )
    (net (code "55") (name "Net-(IC43-A3)") (class "Default")
      (node (ref "IC43") (pin "4") (pinfunction "A3_4") (pintype "input"))
      (node (ref "IC44") (pin "13") (pinfunction "B3_13") (pintype "output"))
      (node (ref "IC45") (pin "19") (pinfunction "B4_19") (pintype "bidirectional"))
      (node (ref "IC45") (pin "20") (pinfunction "B3_20") (pintype "bidirectional"))
    )
    (net (code "56") (name "Net-(IC43-A4)") (class "Default")
      (node (ref "IC43") (pin "5") (pinfunction "A4_5") (pintype "input"))
      (node (ref "IC44") (pin "12") (pinfunction "B4_12") (pintype "output"))
      (node (ref "IC45") (pin "22") (pinfunction "B2_22") (pintype "bidirectional"))
      (node (ref "IC45") (pin "23") (pinfunction "B1_23") (pintype "bidirectional"))
    )
    (net (code "57") (name "Net-(IC43-B5)") (class "Default")
      (node (ref "IC43") (pin "11") (pinfunction "B5_11") (pintype "input"))
      (node (ref "R196") (pin "1") (pinfunction "1_1") (pintype "passive"))
      (node (ref "T26") (pin "3") (pinfunction "D_3") (pintype "passive"))
    )
    (net (code "58") (name "Net-(IC45-DIR)") (class "Default")
      (node (ref "IC45") (pin "24") (pinfunction "DIR_24") (pintype "input"))
      (node (ref "R210") (pin "1") (pinfunction "1_1") (pintype "passive"))
      (node (ref "T27") (pin "3") (pinfunction "D_3") (pintype "passive"))
    )
    (net (code "59") (name "Net-(IC47-1D)") (class "Default")
      (node (ref "IC47") (pin "35") (pinfunction "1D_35") (pintype "input"))
      (node (ref "IC48") (pin "15") (pinfunction "B1_15") (pintype "output"))
    )
    (net (code "60") (name "Net-(IC47-1FSEN)") (class "Default")
      (node (ref "IC47") (pin "20") (pinfunction "3FSEN_20") (pintype "input"))
      (node (ref "IC47") (pin "22") (pinfunction "4FSEN_22") (pintype "input"))
      (node (ref "IC47") (pin "39") (pinfunction "1FSEN_39") (pintype "input"))
      (node (ref "IC47") (pin "41") (pinfunction "2FSEN_41") (pintype "input"))
      (node (ref "R221") (pin "1") (pinfunction "1_1") (pintype "passive"))
      (node (ref "R235") (pin "1") (pinfunction "1_1") (pintype "passive"))
    )
    (net (code "61") (name "Net-(IC47-1R)") (class "Default")
      (node (ref "IC47") (pin "36") (pinfunction "1R_36") (pintype "output"))
      (node (ref "IC50") (pin "2") (pinfunction "A1_2") (pintype "input"))
    )
    (net (code "62") (name "Net-(IC47-2D)") (class "Default")
      (node (ref "IC47") (pin "32") (pinfunction "2D_32") (pintype "input"))
      (node (ref "IC48") (pin "14") (pinfunction "B2_14") (pintype "output"))
    )
    (net (code "63") (name "Net-(IC47-2R)") (class "Default")
      (node (ref "IC47") (pin "33") (pinfunction "2R_33") (pintype "output"))
      (node (ref "IC50") (pin "3") (pinfunction "A2_3") (pintype "input"))
    )
    (net (code "64") (name "Net-(IC47-3D)") (class "Default")
      (node (ref "IC47") (pin "28") (pinfunction "3D_28") (pintype "input"))
      (node (ref "IC48") (pin "13") (pinfunction "B3_13") (pintype "output"))
    )
    (net (code "65") (name "Net-(IC47-3R)") (class "Default")
      (node (ref "IC47") (pin "29") (pinfunction "3R_29") (pintype "output"))
      (node (ref "IC50") (pin "4") (pinfunction "A3_4") (pintype "input"))
    )
    (net (code "66") (name "Net-(IC47-4D)") (class "Default")
      (node (ref "IC47") (pin "25") (pinfunction "4D_25") (pintype "input"))
      (node (ref "IC48") (pin "12") (pinfunction "B4_12") (pintype "output"))
    )
    (net (code "67") (name "Net-(IC47-4R)") (class "Default")
      (node (ref "IC47") (pin "26") (pinfunction "4R_26") (pintype "output"))
      (node (ref "IC50") (pin "5") (pinfunction "A4_5") (pintype "input"))
    )
    (net (code "68") (name "Net-(IC48-A1)") (class "Default")
      (node (ref "IC48") (pin "2") (pinfunction "A1_2") (pintype "input"))
      (node (ref "IC50") (pin "15") (pinfunction "B1_15") (pintype "output"))
      (node (ref "IC51") (pin "14") (pinfunction "B8_14") (pintype "bidirectional"))
      (node (ref "IC51") (pin "15") (pinfunction "B7_15") (pintype "bidirectional"))
    )
    (net (code "69") (name "Net-(IC48-A2)") (class "Default")
      (node (ref "IC48") (pin "3") (pinfunction "A2_3") (pintype "input"))
      (node (ref "IC50") (pin "14") (pinfunction "B2_14") (pintype "output"))
      (node (ref "IC51") (pin "17") (pinfunction "B6_17") (pintype "bidirectional"))
      (node (ref "IC51") (pin "18") (pinfunction "B5_18") (pintype "bidirectional"))
    )
    (net (code "70") (name "Net-(IC48-A3)") (class "Default")
      (node (ref "IC48") (pin "4") (pinfunction "A3_4") (pintype "input"))
      (node (ref "IC50") (pin "13") (pinfunction "B3_13") (pintype "output"))
      (node (ref "IC51") (pin "19") (pinfunction "B4_19") (pintype "bidirectional"))
      (node (ref "IC51") (pin "20") (pinfunction "B3_20") (pintype "bidirectional"))
    )
    (net (code "71") (name "Net-(IC48-A4)") (class "Default")
      (node (ref "IC48") (pin "5") (pinfunction "A4_5") (pintype "input"))
      (node (ref "IC50") (pin "12") (pinfunction "B4_12") (pintype "output"))
      (node (ref "IC51") (pin "22") (pinfunction "B2_22") (pintype "bidirectional"))
      (node (ref "IC51") (pin "23") (pinfunction "B1_23") (pintype "bidirectional"))
    )
    (net (code "72") (name "Net-(IC48-B5)") (class "Default")
      (node (ref "IC48") (pin "11") (pinfunction "B5_11") (pintype "input"))
      (node (ref "R218") (pin "1") (pinfunction "1_1") (pintype "passive"))
      (node (ref "T28") (pin "3") (pinfunction "D_3") (pintype "passive"))
    )
    (net (code "73") (name "Net-(IC49-FB)") (class "Default")
      (node (ref "IC49") (pin "5") (pinfunction "FB_5") (pintype "input"))
      (node (ref "R231") (pin "1") (pinfunction "1_1") (pintype "passive"))
      (node (ref "R237") (pin "2") (pinfunction "2_2") (pintype "passive"))
    )
    (net (code "74") (name "Net-(IC49-SW)") (class "Default")
      (node (ref "IC49") (pin "9") (pinfunction "SW_9") (pintype "output"))
      (node (ref "L17") (pin "1") (pinfunction "1_1") (pintype "passive"))
    )
    (net (code "75") (name "Net-(IC51-DIR)") (class "Default")
      (node (ref "IC51") (pin "24") (pinfunction "DIR_24") (pintype "input"))
      (node (ref "R236") (pin "1") (pinfunction "1_1") (pintype "passive"))
      (node (ref "T29") (pin "3") (pinfunction "D_3") (pintype "passive"))
    )
    (net (code "76") (name "Net-(LD8A-A)") (class "Default")
      (node (ref "LD8") (pin "2") (pinfunction "A_2") (pintype "passive"))
      (node (ref "R194") (pin "2") (pinfunction "2_2") (pintype "passive"))
    )
    (net (code "77") (name "Net-(LD8B-A)") (class "Default")
      (node (ref "LD8") (pin "4") (pinfunction "A_4") (pintype "passive"))
      (node (ref "R195") (pin "2") (pinfunction "2_2") (pintype "passive"))
    )
    (net (code "78") (name "Net-(LD9A-A)") (class "Default")
      (node (ref "LD9") (pin "2") (pinfunction "A_2") (pintype "passive"))
      (node (ref "R213") (pin "2") (pinfunction "2_2") (pintype "passive"))
    )
    (net (code "79") (name "Net-(LD9B-A)") (class "Default")
      (node (ref "LD9") (pin "4") (pinfunction "A_4") (pintype "passive"))
      (node (ref "R214") (pin "2") (pinfunction "2_2") (pintype "passive"))
    )
    (net (code "80") (name "Net-(LD10A-A)") (class "Default")
      (node (ref "LD10") (pin "2") (pinfunction "A_2") (pintype "passive"))
      (node (ref "R215") (pin "2") (pinfunction "2_2") (pintype "passive"))
    )
    (net (code "81") (name "Net-(LD10B-A)") (class "Default")
      (node (ref "LD10") (pin "4") (pinfunction "A_4") (pintype "passive"))
      (node (ref "R216") (pin "2") (pinfunction "2_2") (pintype "passive"))
    )
    (net (code "82") (name "Net-(LD11A-A)") (class "Default")
      (node (ref "LD11") (pin "2") (pinfunction "A_2") (pintype "passive"))
      (node (ref "R217") (pin "2") (pinfunction "2_2") (pintype "passive"))
    )
    (net (code "83") (name "Net-(LD11B-A)") (class "Default")
      (node (ref "LD11") (pin "4") (pinfunction "A_4") (pintype "passive"))
      (node (ref "R220") (pin "2") (pinfunction "2_2") (pintype "passive"))
    )
    (net (code "84") (name "Net-(LD12A-A)") (class "Default")
      (node (ref "LD12") (pin "2") (pinfunction "A_2") (pintype "passive"))
      (node (ref "R238") (pin "2") (pinfunction "2_2") (pintype "passive"))
    )
    (net (code "85") (name "Net-(LD12B-A)") (class "Default")
      (node (ref "LD12") (pin "4") (pinfunction "A_4") (pintype "passive"))
      (node (ref "R239") (pin "2") (pinfunction "2_2") (pintype "passive"))
    )
    (net (code "86") (name "Net-(LD13A-A)") (class "Default")
      (node (ref "LD13") (pin "2") (pinfunction "A_2") (pintype "passive"))
      (node (ref "R240") (pin "2") (pinfunction "2_2") (pintype "passive"))
    )
    (net (code "87") (name "Net-(LD13B-A)") (class "Default")
      (node (ref "LD13") (pin "4") (pinfunction "A_4") (pintype "passive"))
      (node (ref "R241") (pin "2") (pinfunction "2_2") (pintype "passive"))
    )
    (net (code "88") (name "Net-(T10-D)") (class "Default")
      (node (ref "R199") (pin "1") (pinfunction "1_1") (pintype "passive"))
      (node (ref "T10") (pin "3") (pinfunction "D_3") (pintype "passive"))
    )
    (net (code "89") (name "Net-(T11-D)") (class "Default")
      (node (ref "R202") (pin "1") (pinfunction "1_1") (pintype "passive"))
      (node (ref "T11") (pin "3") (pinfunction "D_3") (pintype "passive"))
    )
    (net (code "90") (name "Net-(T12-D)") (class "Default")
      (node (ref "R205") (pin "1") (pinfunction "1_1") (pintype "passive"))
      (node (ref "T12") (pin "3") (pinfunction "D_3") (pintype "passive"))
    )
    (net (code "91") (name "Net-(T13-D)") (class "Default")
      (node (ref "R208") (pin "1") (pinfunction "1_1") (pintype "passive"))
      (node (ref "T13") (pin "3") (pinfunction "D_3") (pintype "passive"))
    )
    (net (code "92") (name "Net-(T14-D)") (class "Default")
      (node (ref "R223") (pin "1") (pinfunction "1_1") (pintype "passive"))
      (node (ref "T14") (pin "3") (pinfunction "D_3") (pintype "passive"))
    )
    (net (code "93") (name "Net-(T15-D)") (class "Default")
      (node (ref "R225") (pin "1") (pinfunction "1_1") (pintype "passive"))
      (node (ref "T15") (pin "3") (pinfunction "D_3") (pintype "passive"))
    )
    (net (code "94") (name "Net-(T16-D)") (class "Default")
      (node (ref "R228") (pin "1") (pinfunction "1_1") (pintype "passive"))
      (node (ref "T16") (pin "3") (pinfunction "D_3") (pintype "passive"))
    )
    (net (code "95") (name "Net-(T17-D)") (class "Default")
      (node (ref "R232") (pin "1") (pinfunction "1_1") (pintype "passive"))
      (node (ref "T17") (pin "3") (pinfunction "D_3") (pintype "passive"))
    )
    (net (code "96") (name "P3V3") (class "Default")
      (node (ref "C171") (pin "2") (pinfunction "2_2") (pintype "passive"))
      (node (ref "C172") (pin "2") (pinfunction "2_2") (pintype "passive"))
      (node (ref "C173") (pin "2") (pinfunction "2_2") (pintype "passive"))
      (node (ref "C174") (pin "2") (pinfunction "2_2") (pintype "passive"))
      (node (ref "C175") (pin "2") (pinfunction "2_2") (pintype "passive"))
      (node (ref "C176") (pin "2") (pinfunction "2_2") (pintype "passive"))
      (node (ref "C177") (pin "2") (pinfunction "2_2") (pintype "passive"))
      (node (ref "C178") (pin "2") (pinfunction "2_2") (pintype "passive"))
      (node (ref "C179") (pin "1") (pinfunction "1_1") (pintype "passive"))
      (node (ref "C180") (pin "2") (pinfunction "2_2") (pintype "passive"))
      (node (ref "C181") (pin "2") (pinfunction "2_2") (pintype "passive"))
      (node (ref "C182") (pin "2") (pinfunction "2_2") (pintype "passive"))
      (node (ref "C183") (pin "2") (pinfunction "2_2") (pintype "passive"))
      (node (ref "C184") (pin "2") (pinfunction "2_2") (pintype "passive"))
      (node (ref "C185") (pin "2") (pinfunction "2_2") (pintype "passive"))
      (node (ref "C186") (pin "2") (pinfunction "2_2") (pintype "passive"))
      (node (ref "C187") (pin "2") (pinfunction "2_2") (pintype "passive"))
      (node (ref "C188") (pin "1") (pinfunction "1_1") (pintype "passive"))
      (node (ref "C189") (pin "2") (pinfunction "2_2") (pintype "passive"))
      (node (ref "C190") (pin "2") (pinfunction "2_2") (pintype "passive"))
      (node (ref "IC41") (pin "11") (pinfunction "VCC_11") (pintype "power_in"))
      (node (ref "IC41") (pin "15") (pinfunction "VCC_15") (pintype "power_in"))
      (node (ref "IC41") (pin "16") (pinfunction "VCC_16") (pintype "power_in"))
      (node (ref "IC41") (pin "2") (pinfunction "VCC_2") (pintype "power_in"))
      (node (ref "IC41") (pin "24") (pinfunction "VCC_24") (pintype "power_in"))
      (node (ref "IC41") (pin "30") (pinfunction "PDN_30") (pintype "input"))
      (node (ref "IC41") (pin "37") (pinfunction "VCC_37") (pintype "power_in"))
      (node (ref "IC41") (pin "45") (pinfunction "VCC_45") (pintype "power_in"))
      (node (ref "IC41") (pin "46") (pinfunction "VCC_46") (pintype "power_in"))
      (node (ref "IC43") (pin "10") (pinfunction "EN2_10") (pintype "input"))
      (node (ref "IC43") (pin "16") (pinfunction "VDD2_16") (pintype "power_in"))
      (node (ref "IC44") (pin "1") (pinfunction "VDD1_1") (pintype "power_in"))
      (node (ref "IC44") (pin "7") (pinfunction "EN1_7") (pintype "input"))
      (node (ref "IC47") (pin "11") (pinfunction "VCC_11") (pintype "power_in"))
      (node (ref "IC47") (pin "15") (pinfunction "VCC_15") (pintype "power_in"))
      (node (ref "IC47") (pin "16") (pinfunction "VCC_16") (pintype "power_in"))
      (node (ref "IC47") (pin "2") (pinfunction "VCC_2") (pintype "power_in"))
      (node (ref "IC47") (pin "24") (pinfunction "VCC_24") (pintype "power_in"))
      (node (ref "IC47") (pin "30") (pinfunction "PDN_30") (pintype "input"))
      (node (ref "IC47") (pin "37") (pinfunction "VCC_37") (pintype "power_in"))
      (node (ref "IC47") (pin "45") (pinfunction "VCC_45") (pintype "power_in"))
      (node (ref "IC47") (pin "46") (pinfunction "VCC_46") (pintype "power_in"))
      (node (ref "IC48") (pin "10") (pinfunction "EN2_10") (pintype "input"))
      (node (ref "IC48") (pin "16") (pinfunction "VDD2_16") (pintype "power_in"))
      (node (ref "IC49") (pin "10") (pinfunction "VOS_10") (pintype "input"))
      (node (ref "IC49") (pin "8") (pinfunction "SLEEP_8") (pintype "input"))
      (node (ref "IC50") (pin "1") (pinfunction "VDD1_1") (pintype "power_in"))
      (node (ref "IC50") (pin "7") (pinfunction "EN1_7") (pintype "input"))
      (node (ref "L17") (pin "2") (pinfunction "2_2") (pintype "passive"))
      (node (ref "R196") (pin "2") (pinfunction "2_2") (pintype "passive"))
      (node (ref "R197") (pin "2") (pinfunction "2_2") (pintype "passive"))
      (node (ref "R218") (pin "2") (pinfunction "2_2") (pintype "passive"))
      (node (ref "R219") (pin "2") (pinfunction "2_2") (pintype "passive"))
      (node (ref "R231") (pin "2") (pinfunction "2_2") (pintype "passive"))
    )
    (net (code "97") (name "P3V3_MP") (class "Default")
      (node (ref "C163") (pin "2") (pinfunction "2_2") (pintype "passive"))
      (node (ref "C200") (pin "2") (pinfunction "2_2") (pintype "passive"))
      (node (ref "IC42") (pin "16") (pinfunction "VCC_16") (pintype "bidirectional"))
      (node (ref "IC42") (pin "2") (pinfunction "A1_2") (pintype "input"))
      (node (ref "IC42") (pin "3") (pinfunction "A2_3") (pintype "input"))
      (node (ref "IC52") (pin "4") (pinfunction "VCC_4") (pintype "power_in"))
      (node (ref "J16") (pin "30") (pinfunction "30_30") (pintype "bidirectional"))
    )
    (net (code "98") (name "P5V0_ISO1") (class "Default")
      (node (ref "C164") (pin "2") (pinfunction "2_2") (pintype "passive"))
      (node (ref "C165") (pin "2") (pinfunction "2_2") (pintype "passive"))
      (node (ref "C166") (pin "2") (pinfunction "2_2") (pintype "passive"))
      (node (ref "C167") (pin "2") (pinfunction "2_2") (pintype "passive"))
      (node (ref "C168") (pin "1") (pinfunction "1_1") (pintype "passive"))
      (node (ref "IC43") (pin "1") (pinfunction "VDD1_1") (pintype "power_in"))
      (node (ref "IC43") (pin "7") (pinfunction "EN1_7") (pintype "input"))
      (node (ref "IC44") (pin "10") (pinfunction "EN2_10") (pintype "input"))
      (node (ref "IC44") (pin "16") (pinfunction "VDD2_16") (pintype "power_in"))
      (node (ref "IC45") (pin "16") (pinfunction "VCC_16") (pintype "power_in"))
      (node (ref "IC45") (pin "21") (pinfunction "VCC_21") (pintype "power_in"))
      (node (ref "IC46") (pin "6") (pinfunction "+Vout_6") (pintype "power_in"))
      (node (ref "R195") (pin "1") (pinfunction "1_1") (pintype "passive"))
      (node (ref "R210") (pin "2") (pinfunction "2_2") (pintype "passive"))
      (node (ref "SW3") (pin "1") (pinfunction "1_1") (pintype "passive"))
      (node (ref "SW3") (pin "2") (pinfunction "2_2") (pintype "passive"))
      (node (ref "SW3") (pin "3") (pinfunction "3_3") (pintype "passive"))
      (node (ref "SW3") (pin "4") (pinfunction "4_4") (pintype "passive"))
    )
    (net (code "99") (name "P5V0_ISO2") (class "Default")
      (node (ref "C195") (pin "2") (pinfunction "2_2") (pintype "passive"))
      (node (ref "C196") (pin "2") (pinfunction "2_2") (pintype "passive"))
      (node (ref "C197") (pin "2") (pinfunction "2_2") (pintype "passive"))
      (node (ref "C198") (pin "2") (pinfunction "2_2") (pintype "passive"))
      (node (ref "C199") (pin "1") (pinfunction "1_1") (pintype "passive"))
      (node (ref "IC48") (pin "1") (pinfunction "VDD1_1") (pintype "power_in"))
      (node (ref "IC48") (pin "7") (pinfunction "EN1_7") (pintype "input"))
      (node (ref "IC50") (pin "10") (pinfunction "EN2_10") (pintype "input"))
      (node (ref "IC50") (pin "16") (pinfunction "VDD2_16") (pintype "power_in"))
      (node (ref "IC51") (pin "16") (pinfunction "VCC_16") (pintype "power_in"))
      (node (ref "IC51") (pin "21") (pinfunction "VCC_21") (pintype "power_in"))
      (node (ref "IC53") (pin "6") (pinfunction "+Vout_6") (pintype "power_in"))
      (node (ref "R220") (pin "1") (pinfunction "1_1") (pintype "passive"))
      (node (ref "R236") (pin "2") (pinfunction "2_2") (pintype "passive"))
      (node (ref "SW2") (pin "1") (pinfunction "1_1") (pintype "passive"))
      (node (ref "SW2") (pin "2") (pinfunction "2_2") (pintype "passive"))
      (node (ref "SW2") (pin "3") (pinfunction "3_3") (pintype "passive"))
      (node (ref "SW2") (pin "4") (pinfunction "4_4") (pintype "passive"))
    )
    (net (code "100") (name "P12V0") (class "Default")
      (node (ref "C169") (pin "2") (pinfunction "2_2") (pintype "passive"))
      (node (ref "C170") (pin "1") (pinfunction "1_1") (pintype "passive"))
      (node (ref "C191") (pin "2") (pinfunction "2_2") (pintype "passive"))
      (node (ref "C192") (pin "2") (pinfunction "2_2") (pintype "passive"))
      (node (ref "C193") (pin "2") (pinfunction "2_2") (pintype "passive"))
      (node (ref "C194") (pin "1") (pinfunction "1_1") (pintype "passive"))
      (node (ref "IC46") (pin "1") (pinfunction "+Vin_1") (pintype "power_in"))
      (node (ref "IC49") (pin "2") (pinfunction "VIN_2") (pintype "input"))
      (node (ref "IC49") (pin "3") (pinfunction "EN_3") (pintype "input"))
      (node (ref "IC53") (pin "1") (pinfunction "+Vin_1") (pintype "power_in"))
      (node (ref "J16") (pin "28") (pinfunction "28_28") (pintype "bidirectional"))
      (node (ref "J16") (pin "29") (pinfunction "29_29") (pintype "bidirectional"))
    )
    (net (code "101") (name "unconnected-(IC41-NC-Pad17)") (class "Default")
      (node (ref "IC41") (pin "17") (pinfunction "NC_17") (pintype "passive"))
    )
    (net (code "102") (name "unconnected-(IC41-NC-Pad44)") (class "Default")
      (node (ref "IC41") (pin "44") (pinfunction "NC_44") (pintype "passive"))
    )
    (net (code "103") (name "unconnected-(IC42-~{INT}-Pad13)") (class "Default")
      (node (ref "IC42") (pin "13") (pinfunction "~{INT}_13") (pintype "output"))
    )
    (net (code "104") (name "unconnected-(IC47-NC-Pad17)") (class "Default")
      (node (ref "IC47") (pin "17") (pinfunction "NC_17") (pintype "passive"))
    )
    (net (code "105") (name "unconnected-(IC47-NC-Pad44)") (class "Default")
      (node (ref "IC47") (pin "44") (pinfunction "NC_44") (pintype "passive"))
    )
    (net (code "106") (name "unconnected-(IC49-NC-Pad4)") (class "Default")
      (node (ref "IC49") (pin "4") (pinfunction "NC_4") (pintype "passive"))
    )
    (net (code "107") (name "unconnected-(IC49-PG-Pad7)") (class "Default")
      (node (ref "IC49") (pin "7") (pinfunction "PG_7") (pintype "output"))
    )
    (net (code "108") (name "unconnected-(IC52-NC-Pad5)") (class "Default")
      (node (ref "IC52") (pin "5") (pinfunction "NC_5") (pintype "passive"))
    )
  )
)
